# dw08aholes.net
KiCad netlist of a schematic drawn in EAGLE
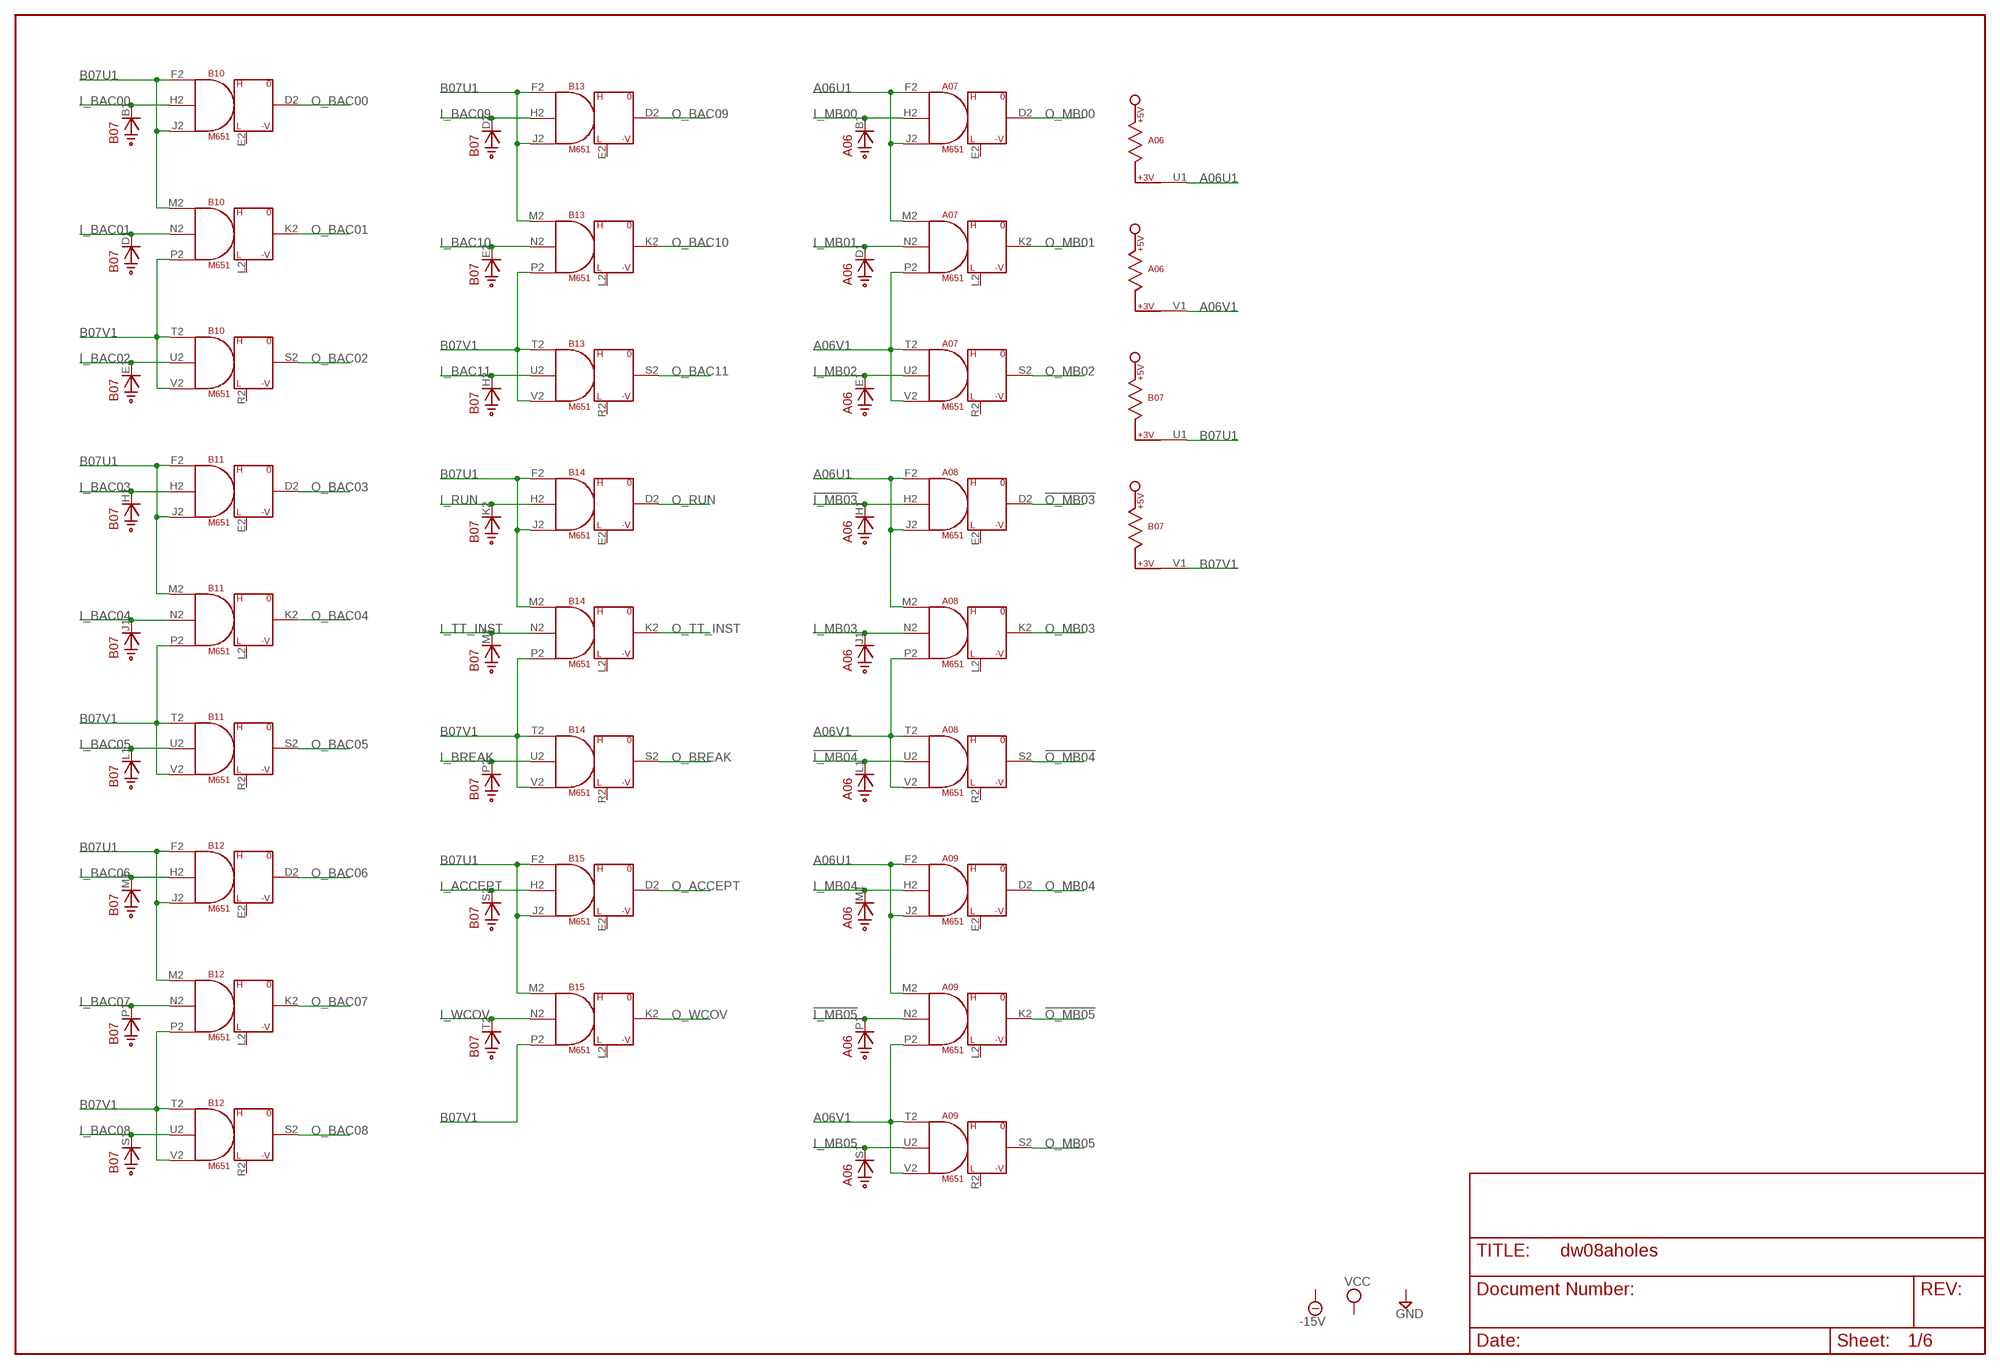
[diagram p0: schematic, sheet 1]
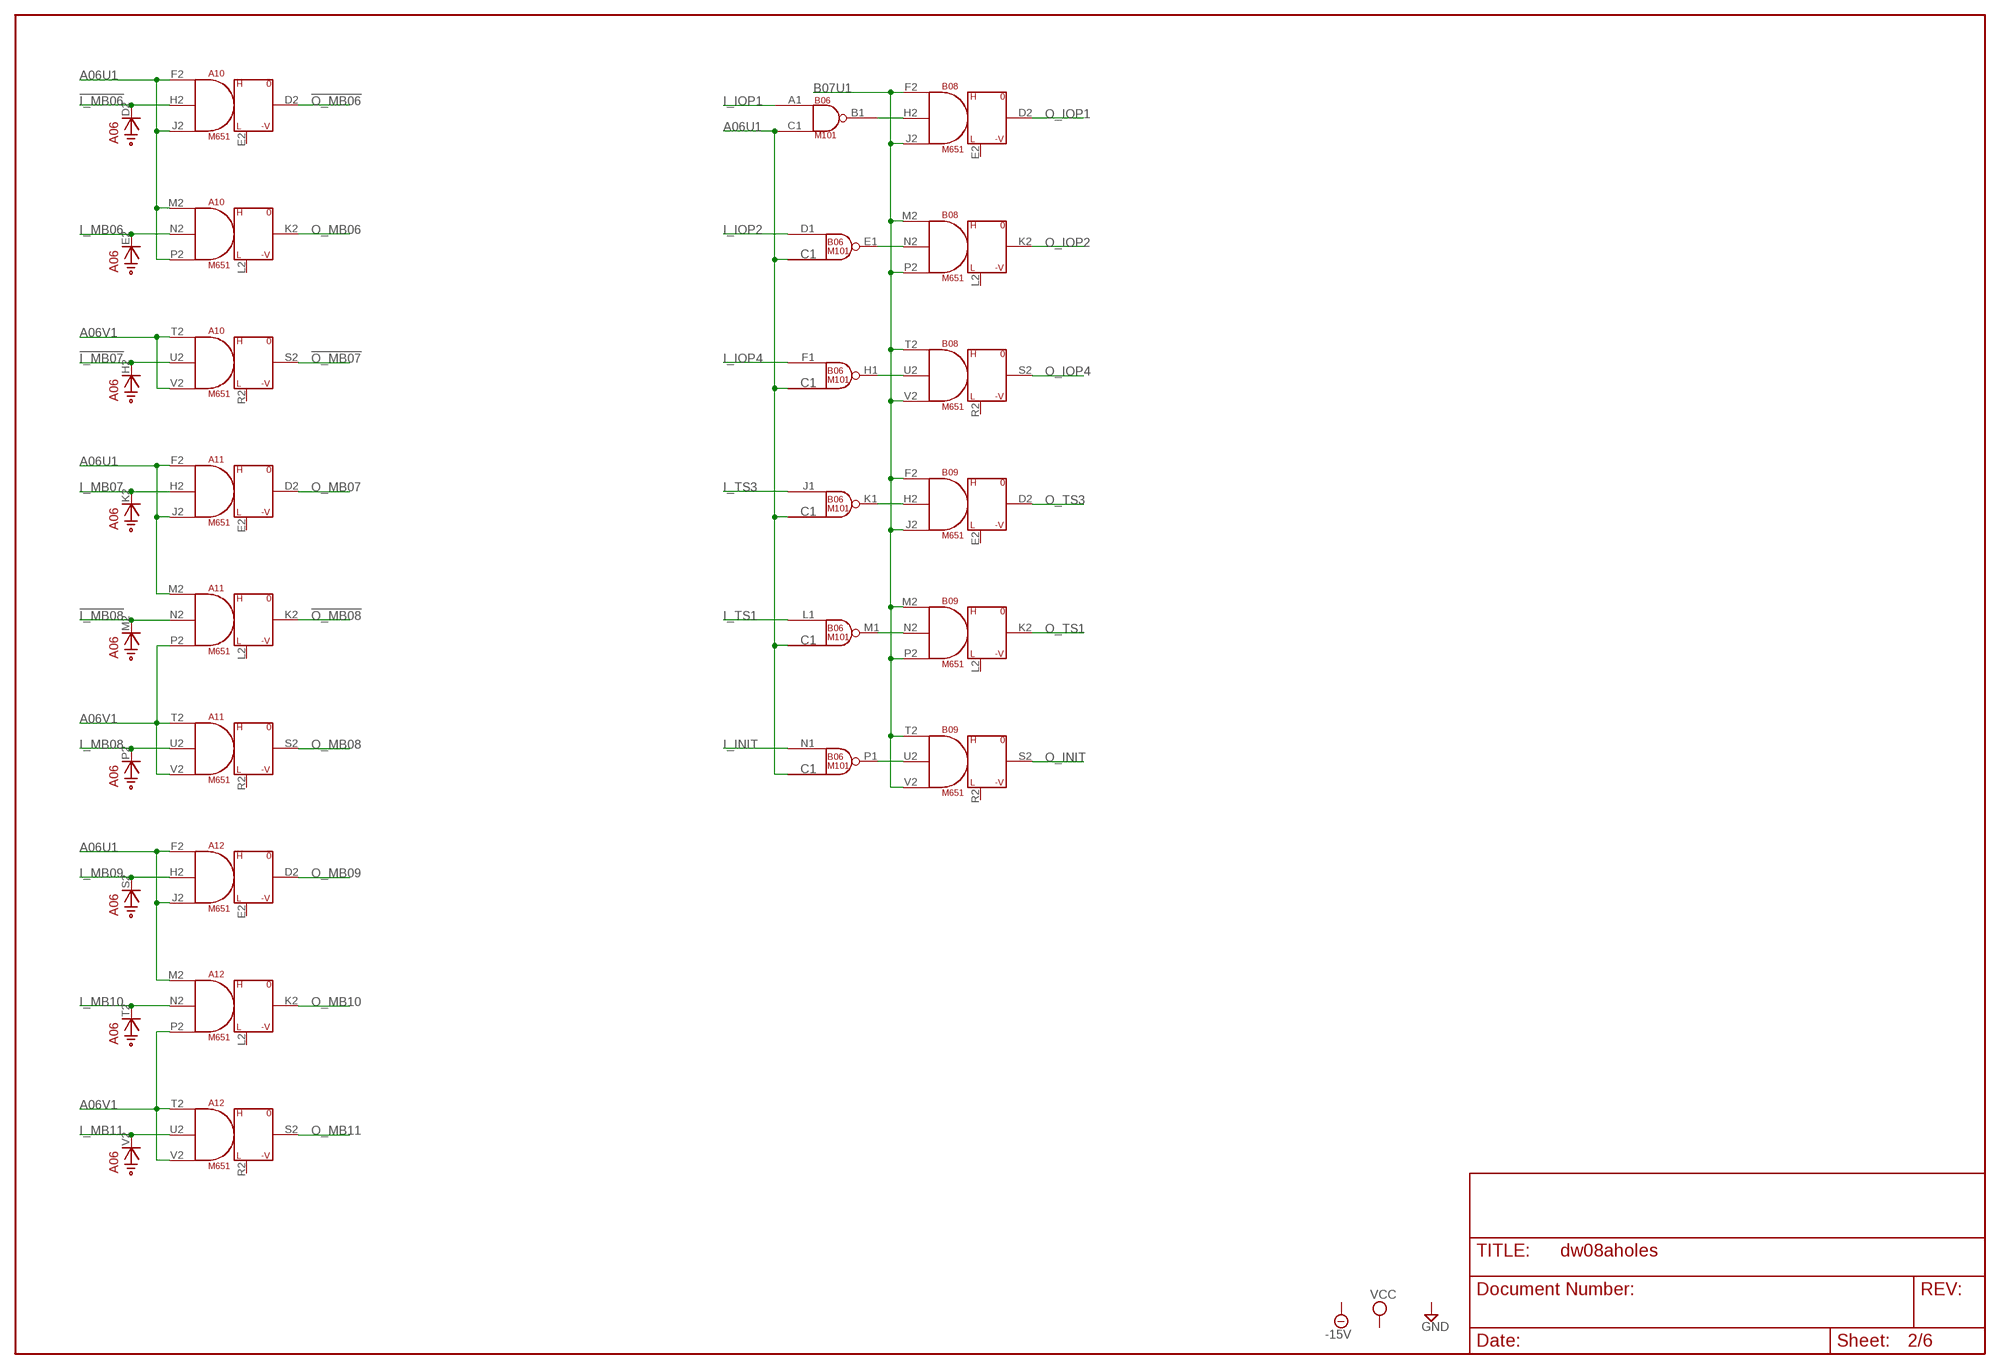
[diagram p1: schematic, sheet 2]
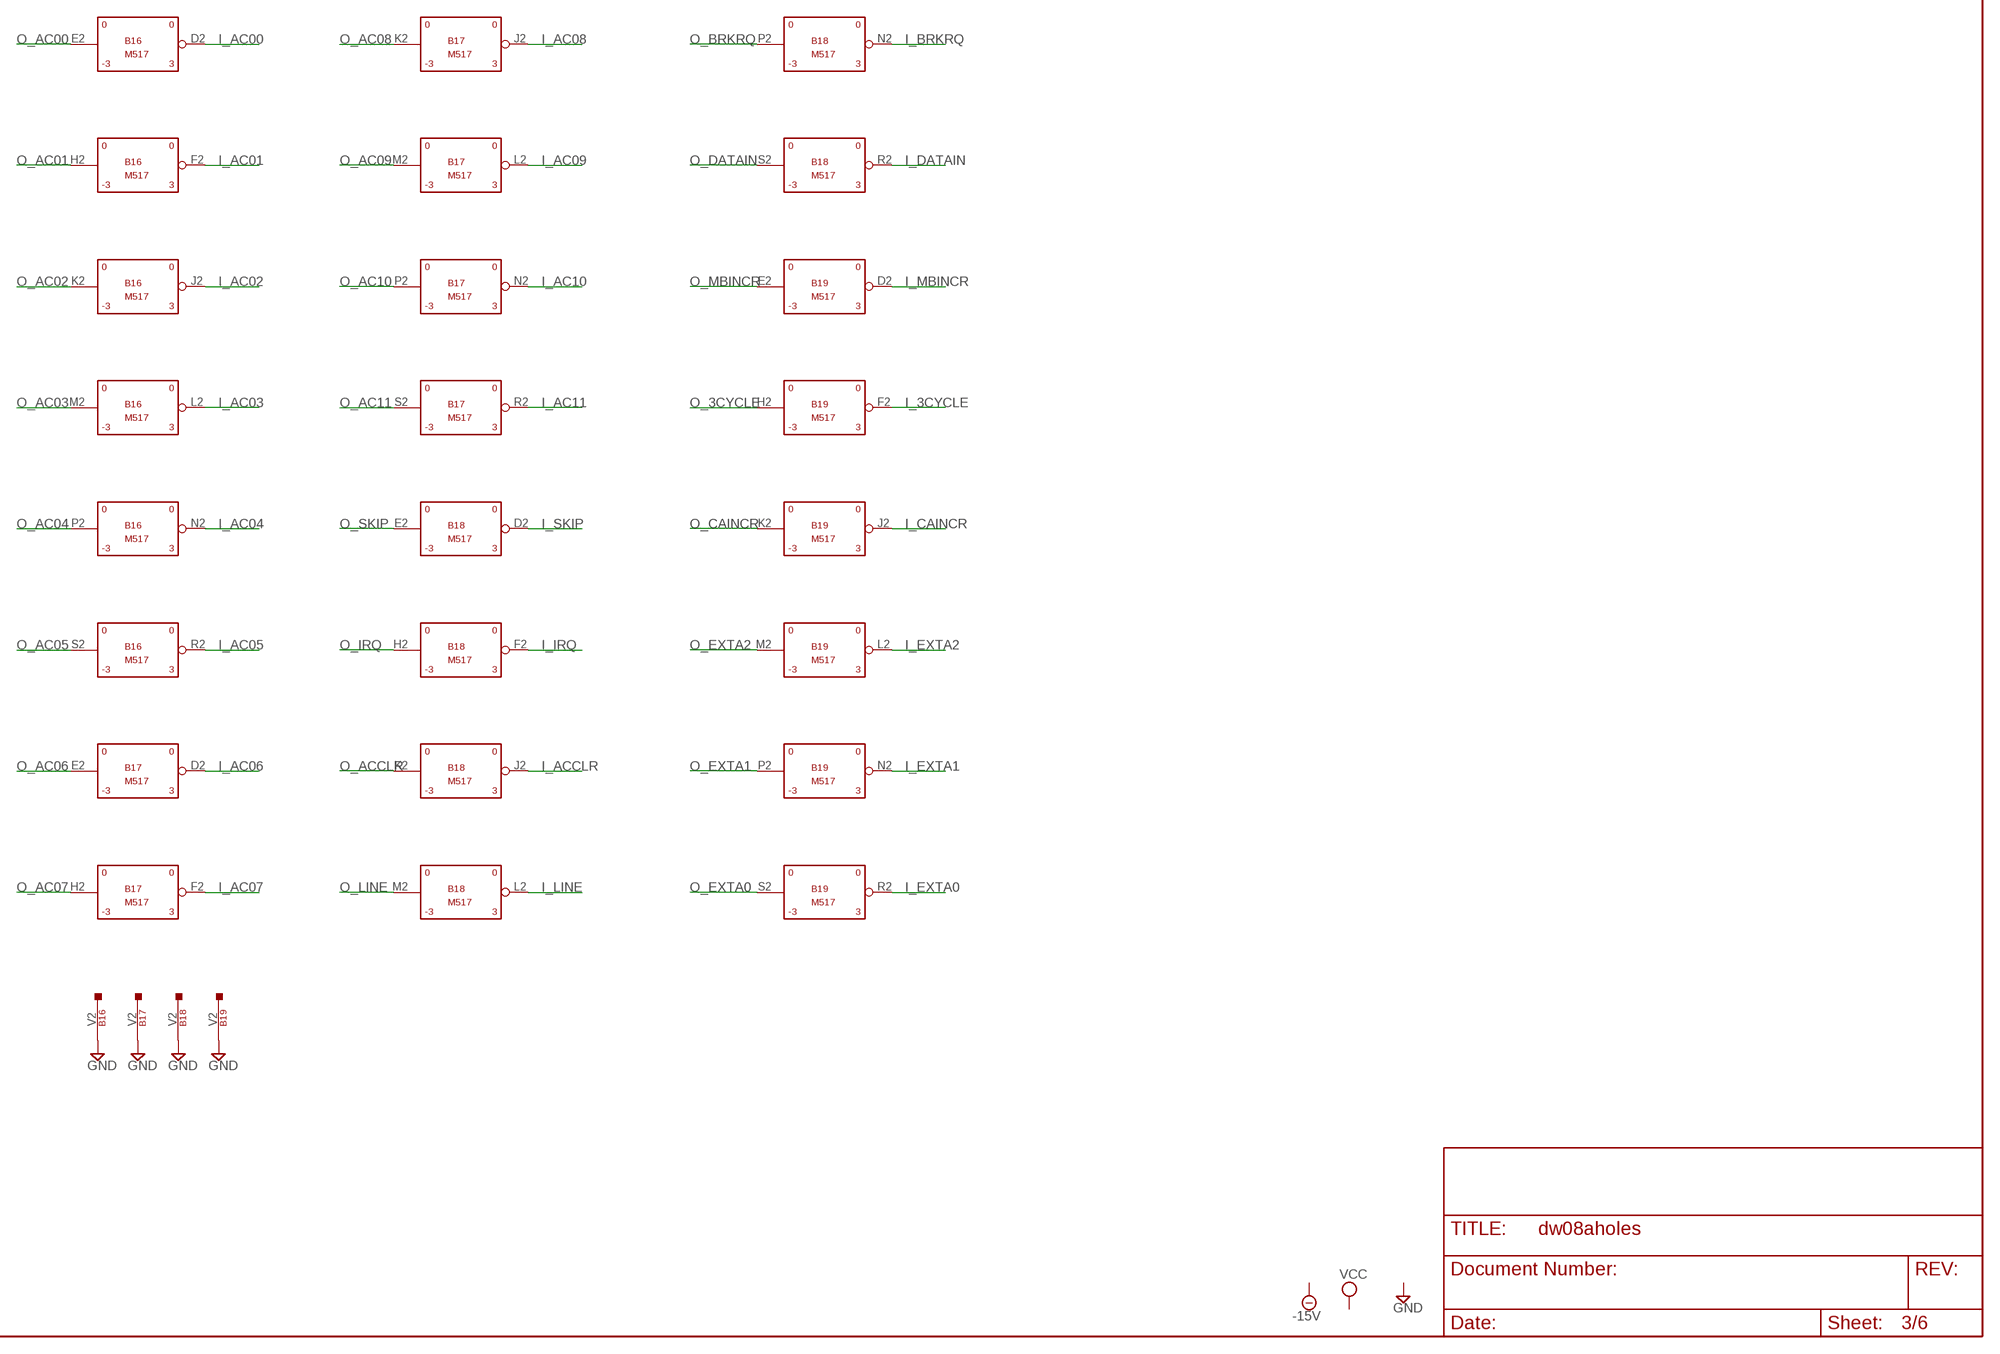
[diagram p2: schematic, sheet 3]
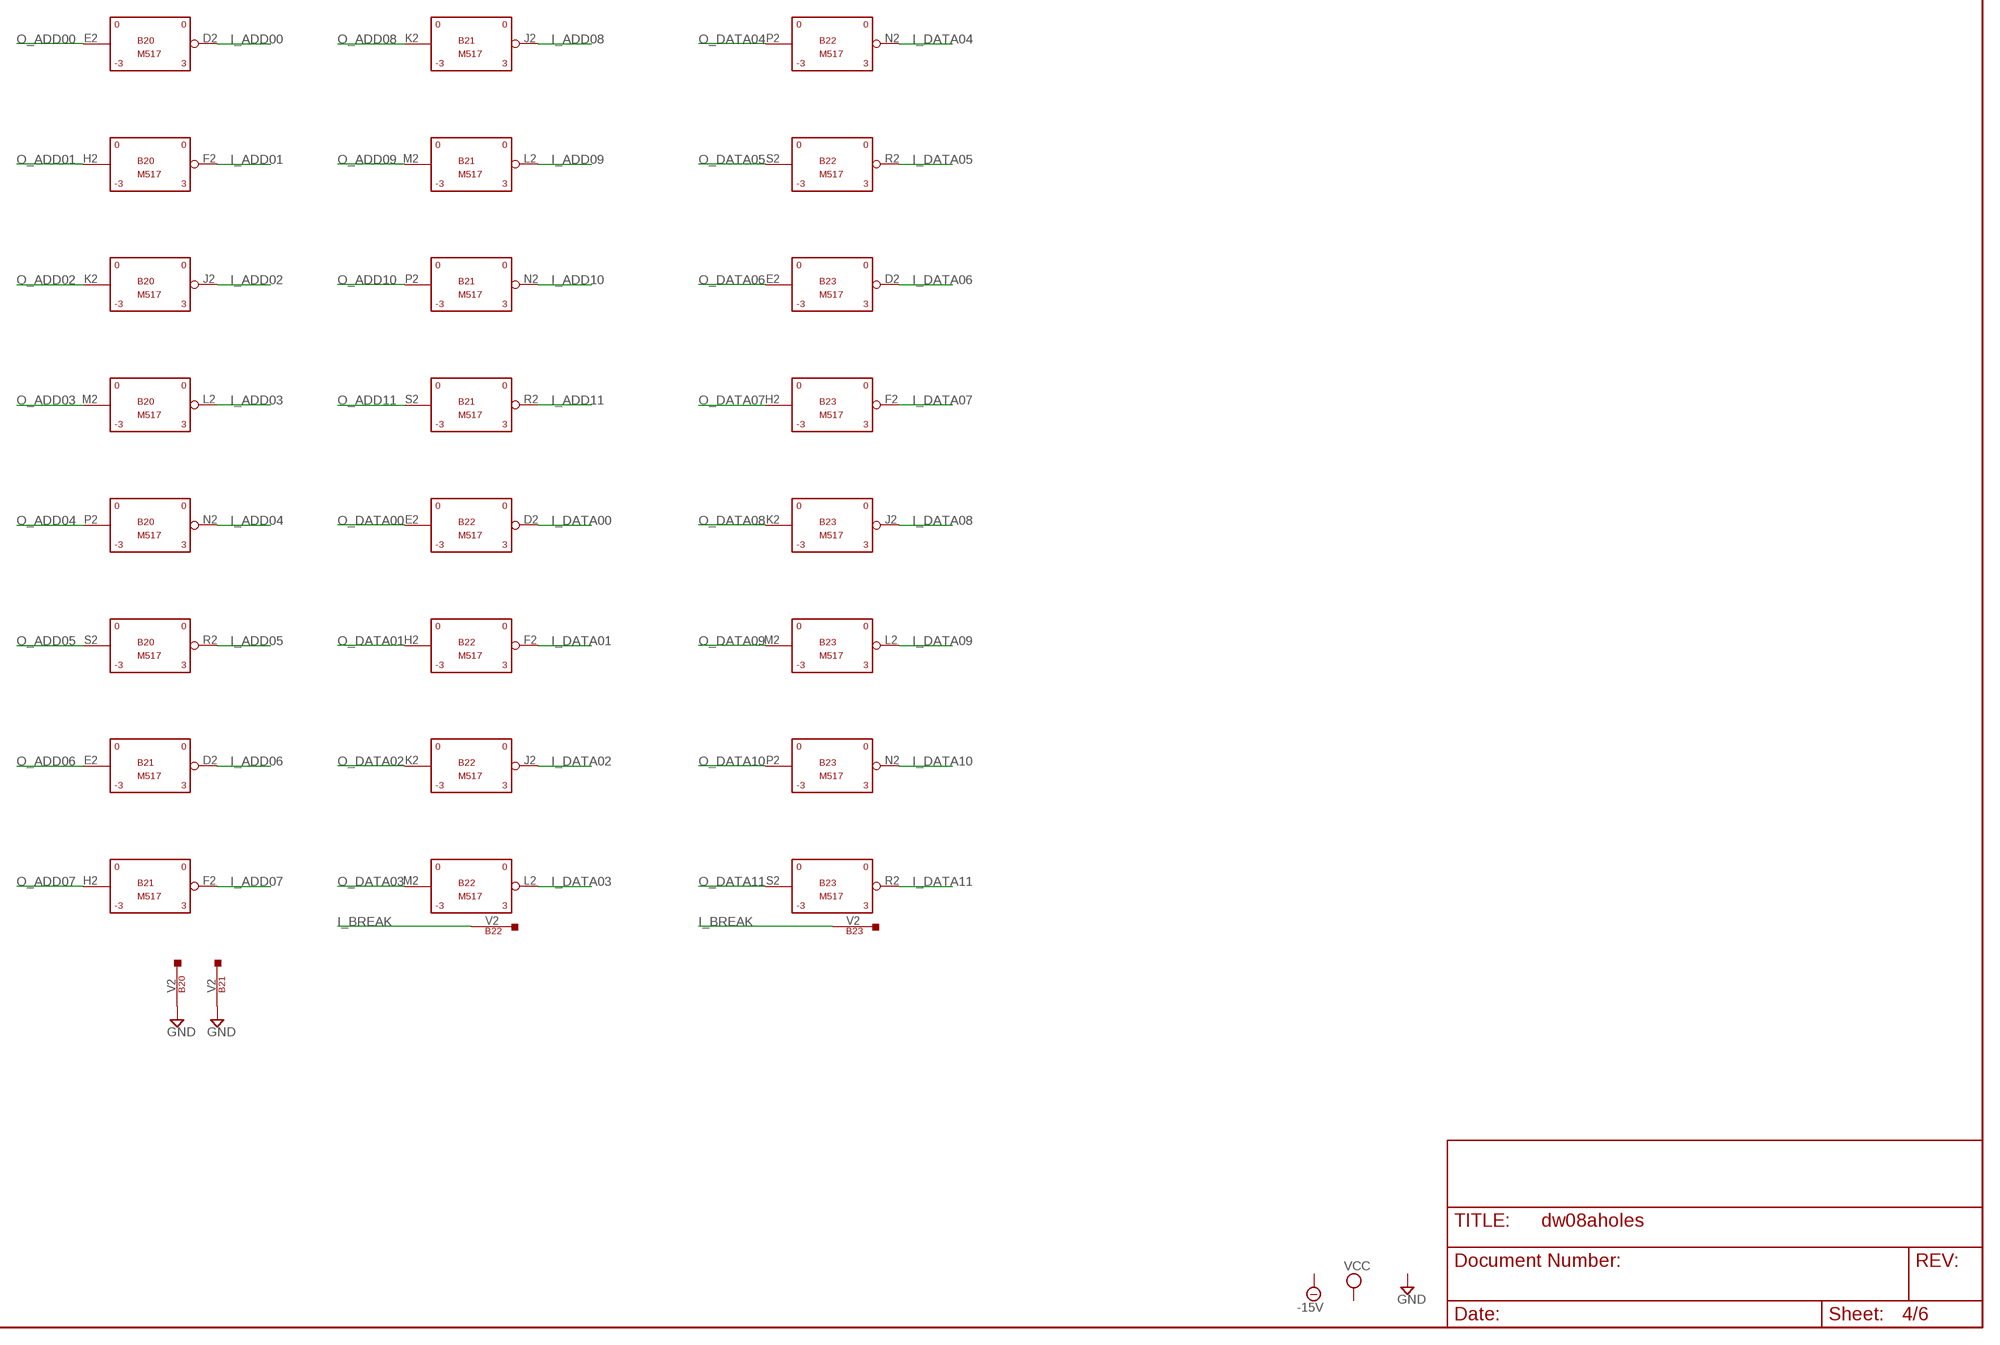
[diagram p3: schematic, sheet 4]
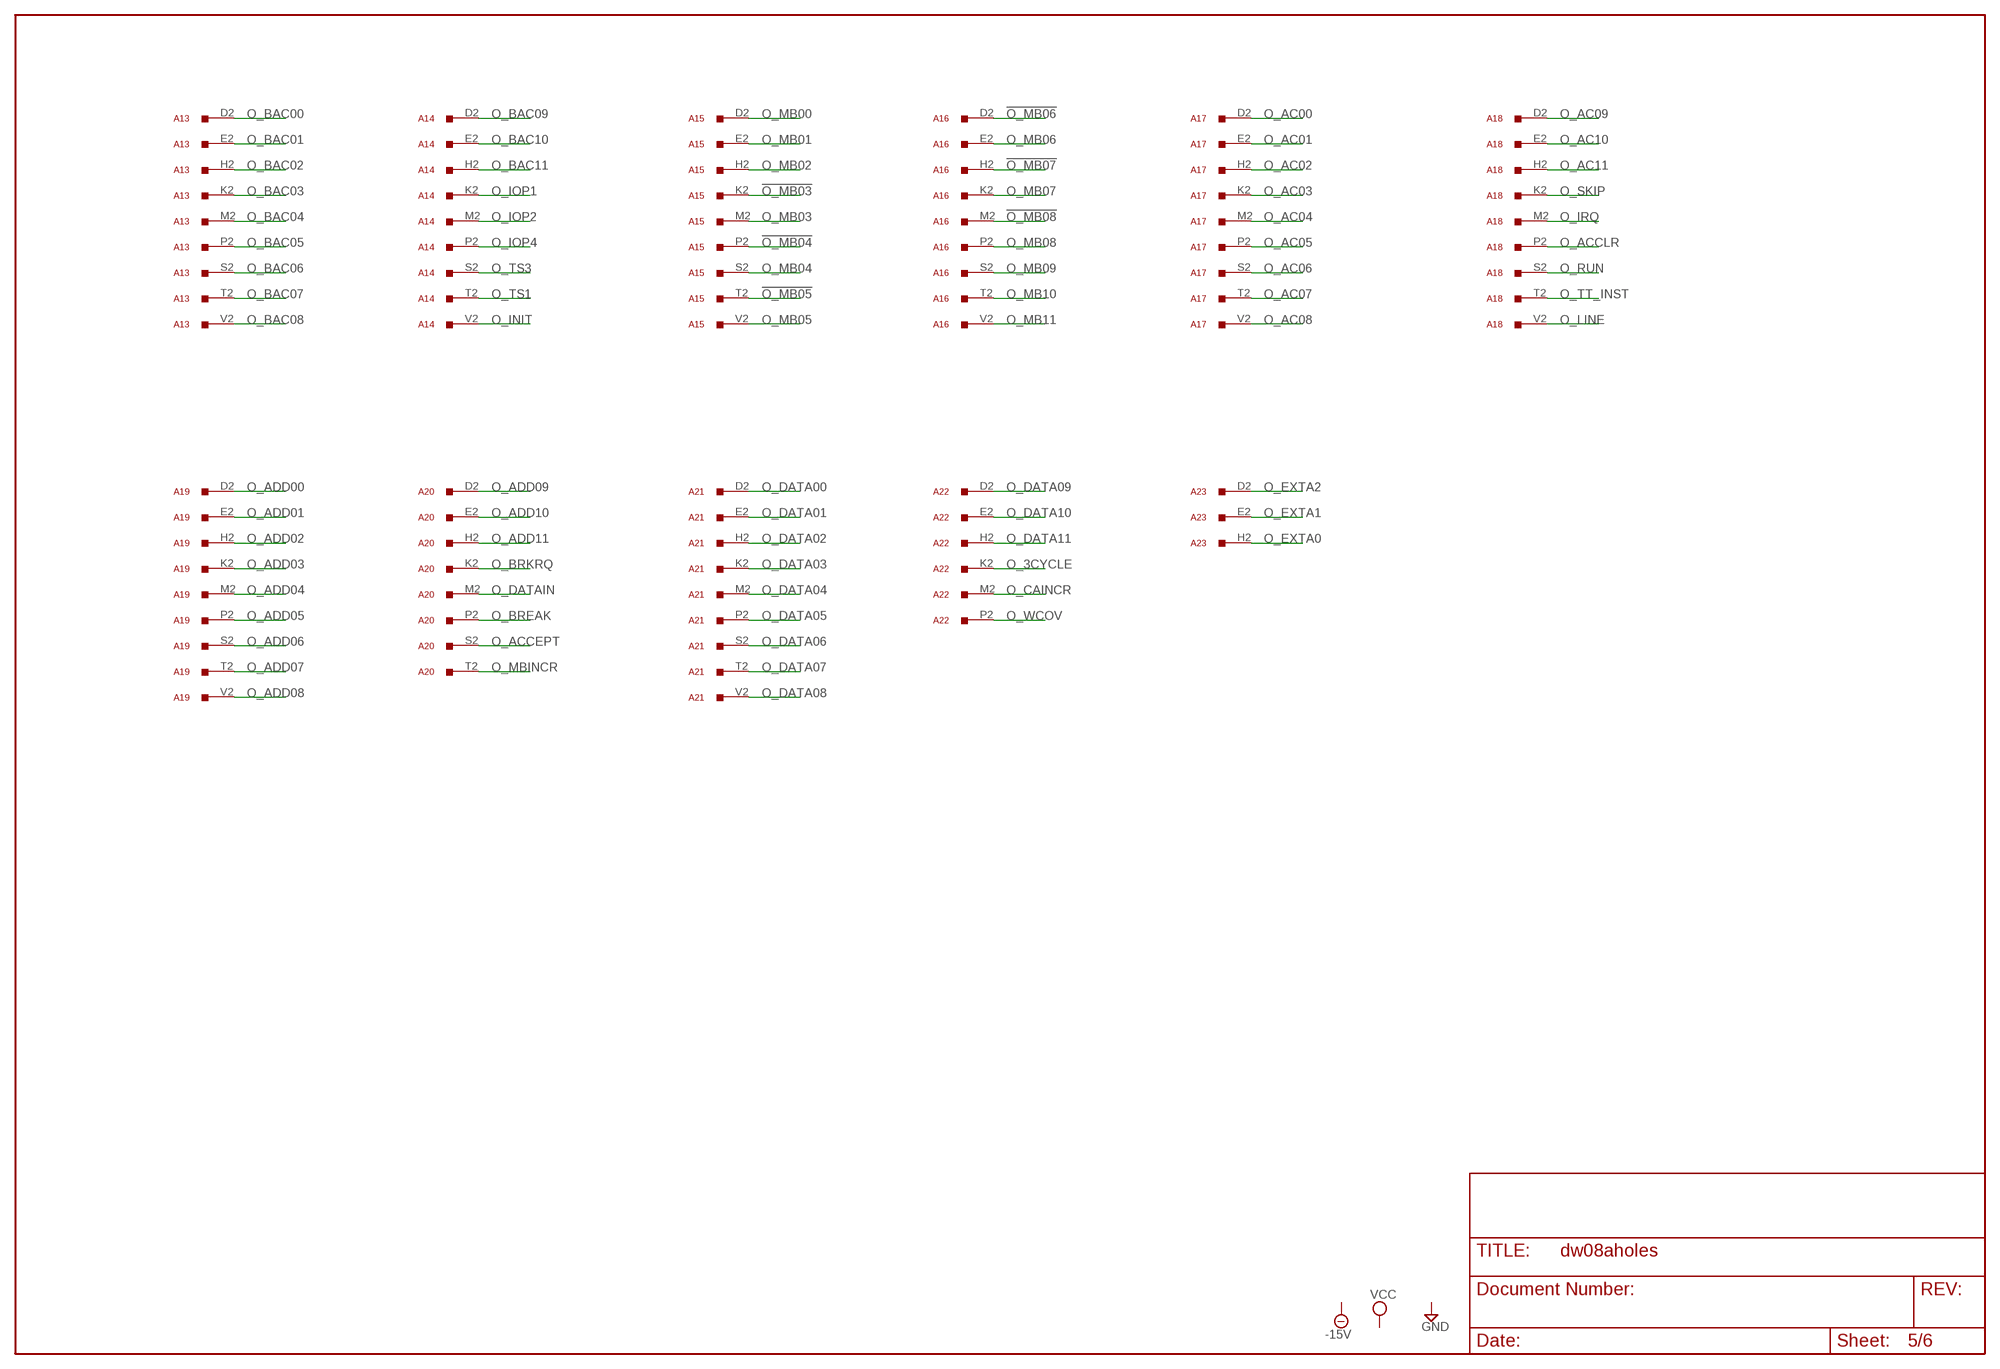
[diagram p4: schematic, sheet 5]
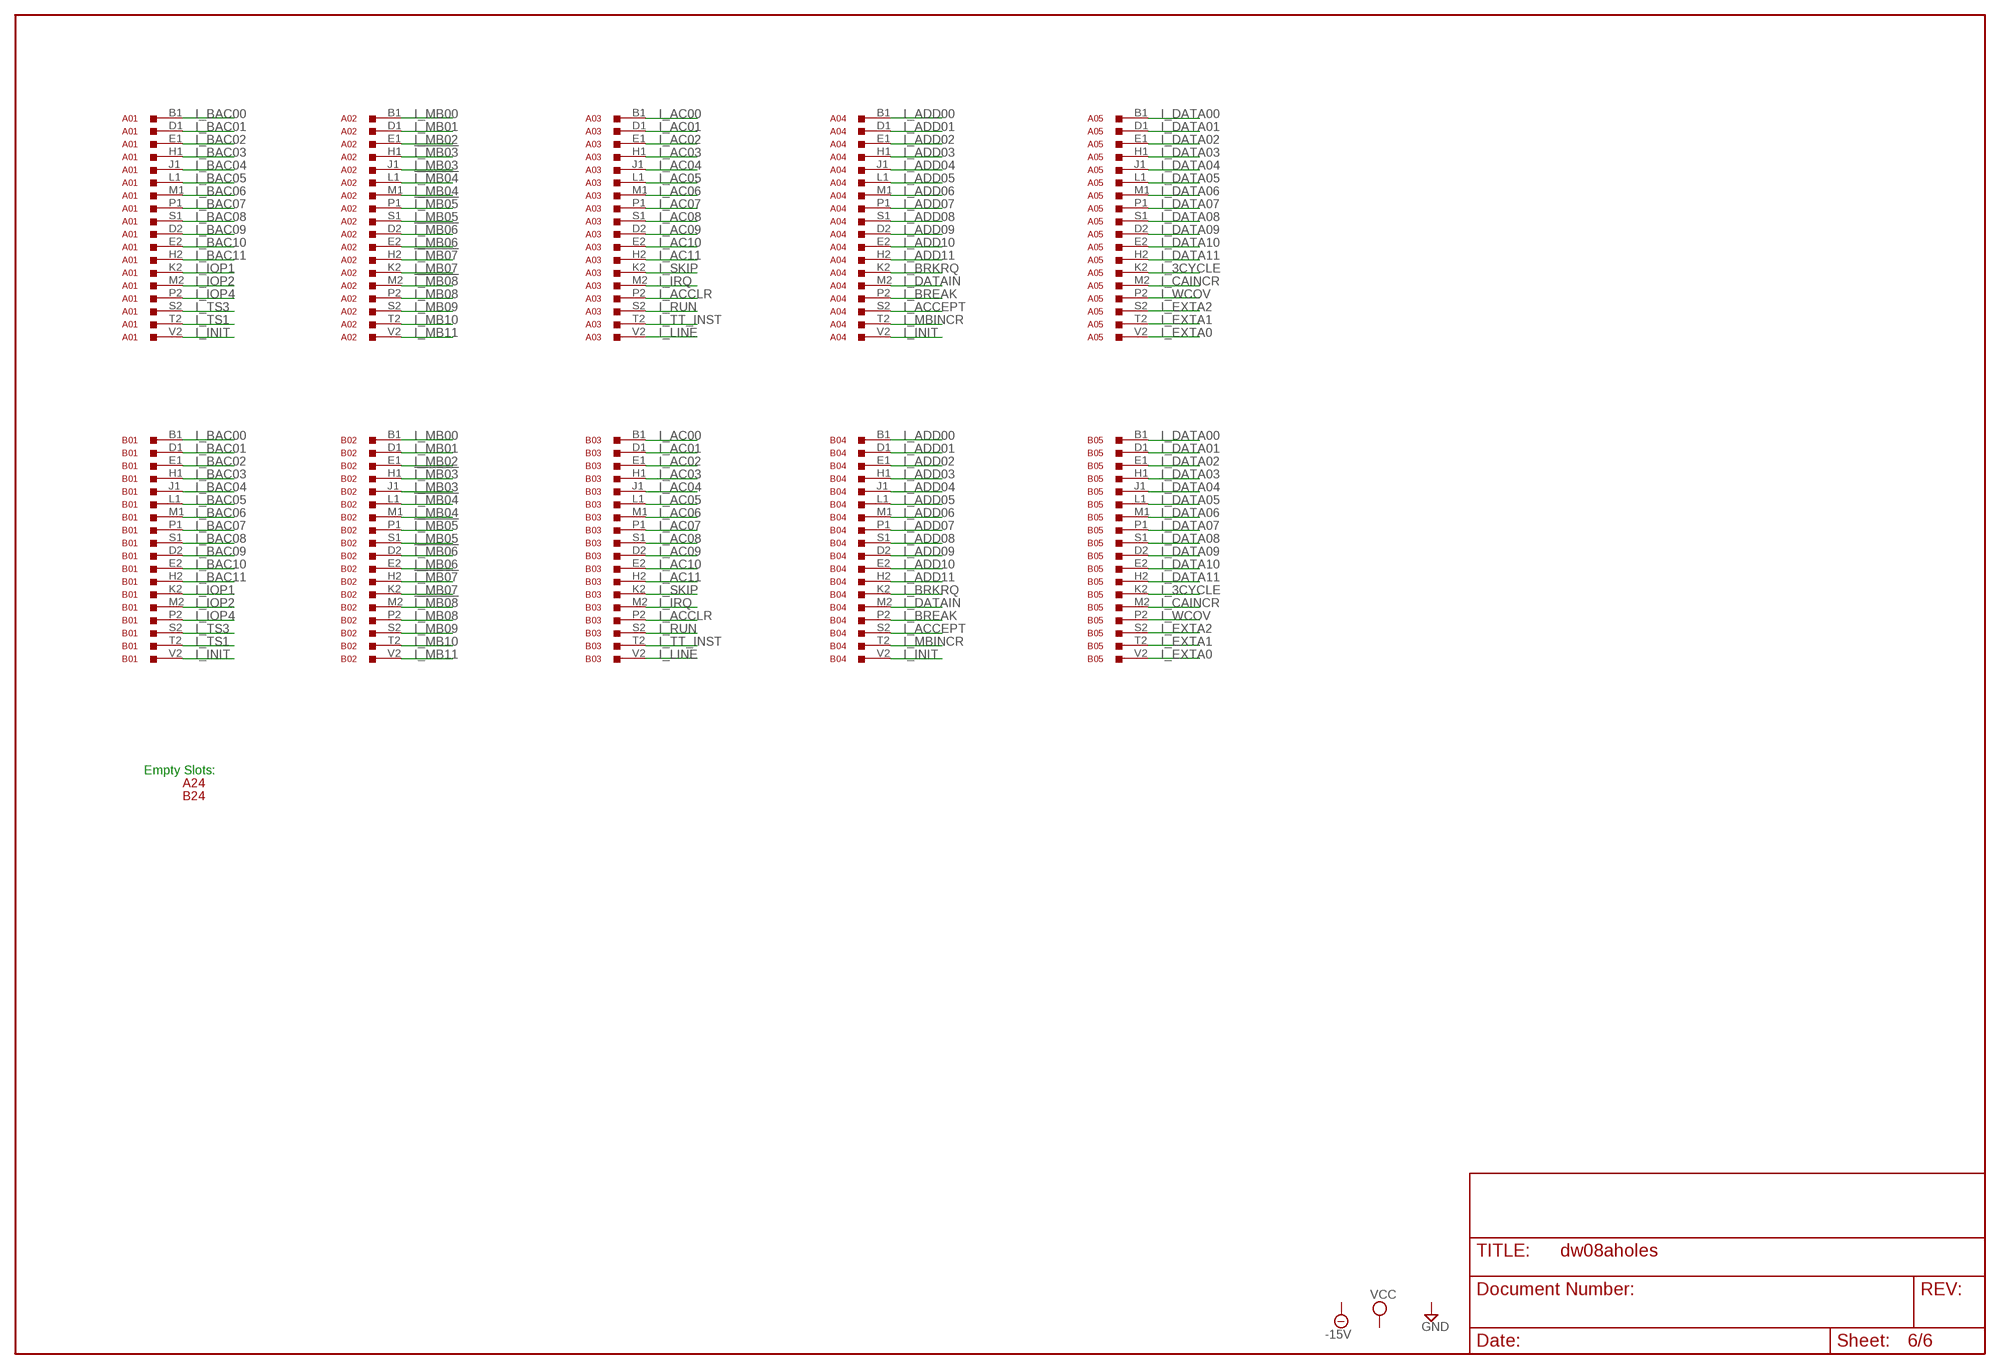
[diagram p5: schematic, sheet 6]

(export (version "E")
  (design (tool "Eeschema 10.0.6"))
  (components
    (comp (ref "A06")
      (value "M907")
      (footprint "eagle-import:H807")
      (libsource (lib "eagle-import") (part "M907"))
    )
    (comp (ref "A10")
      (value "M651")
      (footprint "eagle-import:H807")
      (libsource (lib "eagle-import") (part "M651"))
    )
    (comp (ref "A11")
      (value "M651")
      (footprint "eagle-import:H807")
      (libsource (lib "eagle-import") (part "M651"))
    )
    (comp (ref "A12")
      (value "M651")
      (footprint "eagle-import:H807")
      (libsource (lib "eagle-import") (part "M651"))
    )
    (comp (ref "B06")
      (value "M101")
      (footprint "eagle-import:H807")
      (libsource (lib "eagle-import") (part "M101"))
    )
    (comp (ref "B08")
      (value "M651")
      (footprint "eagle-import:H807")
      (libsource (lib "eagle-import") (part "M651"))
    )
    (comp (ref "B09")
      (value "M651")
      (footprint "eagle-import:H807")
      (libsource (lib "eagle-import") (part "M651"))
    )
    (comp (ref "A13")
      (value "W011")
      (footprint "eagle-import:H807")
      (libsource (lib "eagle-import") (part "W011"))
    )
    (comp (ref "A14")
      (value "W011")
      (footprint "eagle-import:H807")
      (libsource (lib "eagle-import") (part "W011"))
    )
    (comp (ref "A15")
      (value "W011")
      (footprint "eagle-import:H807")
      (libsource (lib "eagle-import") (part "W011"))
    )
    (comp (ref "A16")
      (value "W011")
      (footprint "eagle-import:H807")
      (libsource (lib "eagle-import") (part "W011"))
    )
    (comp (ref "A17")
      (value "W011")
      (footprint "eagle-import:H807")
      (libsource (lib "eagle-import") (part "W011"))
    )
    (comp (ref "A18")
      (value "W011")
      (footprint "eagle-import:H807")
      (libsource (lib "eagle-import") (part "W011"))
    )
    (comp (ref "A19")
      (value "W011")
      (footprint "eagle-import:H807")
      (libsource (lib "eagle-import") (part "W011"))
    )
    (comp (ref "A20")
      (value "W011")
      (footprint "eagle-import:H807")
      (libsource (lib "eagle-import") (part "W011"))
    )
    (comp (ref "A21")
      (value "W011")
      (footprint "eagle-import:H807")
      (libsource (lib "eagle-import") (part "W011"))
    )
    (comp (ref "A22")
      (value "W011")
      (footprint "eagle-import:H807")
      (libsource (lib "eagle-import") (part "W011"))
    )
    (comp (ref "A23")
      (value "W011")
      (footprint "eagle-import:H807")
      (libsource (lib "eagle-import") (part "W011"))
    )
    (comp (ref "B20")
      (value "M517")
      (footprint "eagle-import:H807")
      (libsource (lib "eagle-import") (part "M517"))
    )
    (comp (ref "B21")
      (value "M517")
      (footprint "eagle-import:H807")
      (libsource (lib "eagle-import") (part "M517"))
    )
    (comp (ref "B22")
      (value "M517")
      (footprint "eagle-import:H807")
      (libsource (lib "eagle-import") (part "M517"))
    )
    (comp (ref "B23")
      (value "M517")
      (footprint "eagle-import:H807")
      (libsource (lib "eagle-import") (part "M517"))
    )
    (comp (ref "A07")
      (value "M651")
      (footprint "eagle-import:H807")
      (libsource (lib "eagle-import") (part "M651"))
    )
    (comp (ref "A08")
      (value "M651")
      (footprint "eagle-import:H807")
      (libsource (lib "eagle-import") (part "M651"))
    )
    (comp (ref "A09")
      (value "M651")
      (footprint "eagle-import:H807")
      (libsource (lib "eagle-import") (part "M651"))
    )
    (comp (ref "B07")
      (value "M907")
      (footprint "eagle-import:H807")
      (libsource (lib "eagle-import") (part "M907"))
    )
    (comp (ref "B10")
      (value "M651")
      (footprint "eagle-import:H807")
      (libsource (lib "eagle-import") (part "M651"))
    )
    (comp (ref "B11")
      (value "M651")
      (footprint "eagle-import:H807")
      (libsource (lib "eagle-import") (part "M651"))
    )
    (comp (ref "B12")
      (value "M651")
      (footprint "eagle-import:H807")
      (libsource (lib "eagle-import") (part "M651"))
    )
    (comp (ref "B13")
      (value "M651")
      (footprint "eagle-import:H807")
      (libsource (lib "eagle-import") (part "M651"))
    )
    (comp (ref "B14")
      (value "M651")
      (footprint "eagle-import:H807")
      (libsource (lib "eagle-import") (part "M651"))
    )
    (comp (ref "B15")
      (value "M651")
      (footprint "eagle-import:H807")
      (libsource (lib "eagle-import") (part "M651"))
    )
    (comp (ref "A01")
      (value "M903")
      (footprint "eagle-import:H807")
      (libsource (lib "eagle-import") (part "M903"))
    )
    (comp (ref "A02")
      (value "M903")
      (footprint "eagle-import:H807")
      (libsource (lib "eagle-import") (part "M903"))
    )
    (comp (ref "A03")
      (value "M903")
      (footprint "eagle-import:H807")
      (libsource (lib "eagle-import") (part "M903"))
    )
    (comp (ref "A04")
      (value "M903")
      (footprint "eagle-import:H807")
      (libsource (lib "eagle-import") (part "M903"))
    )
    (comp (ref "A05")
      (value "M903")
      (footprint "eagle-import:H807")
      (libsource (lib "eagle-import") (part "M903"))
    )
    (comp (ref "A24")
      (value "H807")
      (footprint "eagle-import:H807")
      (libsource (lib "eagle-import") (part "H807"))
    )
    (comp (ref "B01")
      (value "M903")
      (footprint "eagle-import:H807")
      (libsource (lib "eagle-import") (part "M903"))
    )
    (comp (ref "B02")
      (value "M903")
      (footprint "eagle-import:H807")
      (libsource (lib "eagle-import") (part "M903"))
    )
    (comp (ref "B03")
      (value "M903")
      (footprint "eagle-import:H807")
      (libsource (lib "eagle-import") (part "M903"))
    )
    (comp (ref "B04")
      (value "M903")
      (footprint "eagle-import:H807")
      (libsource (lib "eagle-import") (part "M903"))
    )
    (comp (ref "B05")
      (value "M903")
      (footprint "eagle-import:H807")
      (libsource (lib "eagle-import") (part "M903"))
    )
    (comp (ref "B24")
      (value "H807")
      (footprint "eagle-import:H807")
      (libsource (lib "eagle-import") (part "H807"))
    )
    (comp (ref "B16")
      (value "M517")
      (footprint "eagle-import:H807")
      (libsource (lib "eagle-import") (part "M517"))
    )
    (comp (ref "B17")
      (value "M517")
      (footprint "eagle-import:H807")
      (libsource (lib "eagle-import") (part "M517"))
    )
    (comp (ref "B18")
      (value "M517")
      (footprint "eagle-import:H807")
      (libsource (lib "eagle-import") (part "M517"))
    )
    (comp (ref "B19")
      (value "M517")
      (footprint "eagle-import:H807")
      (libsource (lib "eagle-import") (part "M517"))
    )
  )
  (nets
    (net (code "2") (name "A06U1") (class "Default")
      (node (ref "A06") (pin "U1") (pinfunction "P$1_U1") (pintype "passive"))
      (node (ref "A07") (pin "F2") (pinfunction "IN1_F2") (pintype "input"))
      (node (ref "A07") (pin "J2") (pinfunction "IN3_J2") (pintype "input"))
      (node (ref "A07") (pin "M2") (pinfunction "IN1_M2") (pintype "input"))
      (node (ref "A08") (pin "F2") (pinfunction "IN1_F2") (pintype "input"))
      (node (ref "A08") (pin "J2") (pinfunction "IN3_J2") (pintype "input"))
      (node (ref "A08") (pin "M2") (pinfunction "IN1_M2") (pintype "input"))
      (node (ref "A09") (pin "F2") (pinfunction "IN1_F2") (pintype "input"))
      (node (ref "A09") (pin "J2") (pinfunction "IN3_J2") (pintype "input"))
      (node (ref "A09") (pin "M2") (pinfunction "IN1_M2") (pintype "input"))
      (node (ref "A10") (pin "F2") (pinfunction "IN1_F2") (pintype "input"))
      (node (ref "A10") (pin "J2") (pinfunction "IN3_J2") (pintype "input"))
      (node (ref "A10") (pin "M2") (pinfunction "IN1_M2") (pintype "input"))
      (node (ref "A10") (pin "P2") (pinfunction "IN3_P2") (pintype "input"))
      (node (ref "A11") (pin "F2") (pinfunction "IN1_F2") (pintype "input"))
      (node (ref "A11") (pin "J2") (pinfunction "IN3_J2") (pintype "input"))
      (node (ref "A11") (pin "M2") (pinfunction "IN1_M2") (pintype "input"))
      (node (ref "A12") (pin "F2") (pinfunction "IN1_F2") (pintype "input"))
      (node (ref "A12") (pin "J2") (pinfunction "IN3_J2") (pintype "input"))
      (node (ref "A12") (pin "M2") (pinfunction "IN1_M2") (pintype "input"))
      (node (ref "B06") (pin "C1") (pinfunction "IN2_C1") (pintype "input"))
    )
    (net (code "3") (name "A06V1") (class "Default")
      (node (ref "A06") (pin "V1") (pinfunction "P$1_V1") (pintype "passive"))
      (node (ref "A07") (pin "P2") (pinfunction "IN3_P2") (pintype "input"))
      (node (ref "A07") (pin "T2") (pinfunction "IN1_T2") (pintype "input"))
      (node (ref "A07") (pin "V2") (pinfunction "IN3_V2") (pintype "input"))
      (node (ref "A08") (pin "P2") (pinfunction "IN3_P2") (pintype "input"))
      (node (ref "A08") (pin "T2") (pinfunction "IN1_T2") (pintype "input"))
      (node (ref "A08") (pin "V2") (pinfunction "IN3_V2") (pintype "input"))
      (node (ref "A09") (pin "P2") (pinfunction "IN3_P2") (pintype "input"))
      (node (ref "A09") (pin "T2") (pinfunction "IN1_T2") (pintype "input"))
      (node (ref "A09") (pin "V2") (pinfunction "IN3_V2") (pintype "input"))
      (node (ref "A10") (pin "T2") (pinfunction "IN1_T2") (pintype "input"))
      (node (ref "A10") (pin "V2") (pinfunction "IN3_V2") (pintype "input"))
      (node (ref "A11") (pin "P2") (pinfunction "IN3_P2") (pintype "input"))
      (node (ref "A11") (pin "T2") (pinfunction "IN1_T2") (pintype "input"))
      (node (ref "A11") (pin "V2") (pinfunction "IN3_V2") (pintype "input"))
      (node (ref "A12") (pin "P2") (pinfunction "IN3_P2") (pintype "input"))
      (node (ref "A12") (pin "T2") (pinfunction "IN1_T2") (pintype "input"))
      (node (ref "A12") (pin "V2") (pinfunction "IN3_V2") (pintype "input"))
    )
    (net (code "4") (name "B07U1") (class "Default")
      (node (ref "B07") (pin "U1") (pinfunction "P$1_U1") (pintype "passive"))
      (node (ref "B08") (pin "F2") (pinfunction "IN1_F2") (pintype "input"))
      (node (ref "B08") (pin "J2") (pinfunction "IN3_J2") (pintype "input"))
      (node (ref "B08") (pin "M2") (pinfunction "IN1_M2") (pintype "input"))
      (node (ref "B08") (pin "P2") (pinfunction "IN3_P2") (pintype "input"))
      (node (ref "B08") (pin "T2") (pinfunction "IN1_T2") (pintype "input"))
      (node (ref "B08") (pin "V2") (pinfunction "IN3_V2") (pintype "input"))
      (node (ref "B09") (pin "F2") (pinfunction "IN1_F2") (pintype "input"))
      (node (ref "B09") (pin "J2") (pinfunction "IN3_J2") (pintype "input"))
      (node (ref "B09") (pin "M2") (pinfunction "IN1_M2") (pintype "input"))
      (node (ref "B09") (pin "P2") (pinfunction "IN3_P2") (pintype "input"))
      (node (ref "B09") (pin "T2") (pinfunction "IN1_T2") (pintype "input"))
      (node (ref "B09") (pin "V2") (pinfunction "IN3_V2") (pintype "input"))
      (node (ref "B10") (pin "F2") (pinfunction "IN1_F2") (pintype "input"))
      (node (ref "B10") (pin "J2") (pinfunction "IN3_J2") (pintype "input"))
      (node (ref "B10") (pin "M2") (pinfunction "IN1_M2") (pintype "input"))
      (node (ref "B11") (pin "F2") (pinfunction "IN1_F2") (pintype "input"))
      (node (ref "B11") (pin "J2") (pinfunction "IN3_J2") (pintype "input"))
      (node (ref "B11") (pin "M2") (pinfunction "IN1_M2") (pintype "input"))
      (node (ref "B12") (pin "F2") (pinfunction "IN1_F2") (pintype "input"))
      (node (ref "B12") (pin "J2") (pinfunction "IN3_J2") (pintype "input"))
      (node (ref "B12") (pin "M2") (pinfunction "IN1_M2") (pintype "input"))
      (node (ref "B13") (pin "F2") (pinfunction "IN1_F2") (pintype "input"))
      (node (ref "B13") (pin "J2") (pinfunction "IN3_J2") (pintype "input"))
      (node (ref "B13") (pin "M2") (pinfunction "IN1_M2") (pintype "input"))
      (node (ref "B14") (pin "F2") (pinfunction "IN1_F2") (pintype "input"))
      (node (ref "B14") (pin "J2") (pinfunction "IN3_J2") (pintype "input"))
      (node (ref "B14") (pin "M2") (pinfunction "IN1_M2") (pintype "input"))
      (node (ref "B15") (pin "F2") (pinfunction "IN1_F2") (pintype "input"))
      (node (ref "B15") (pin "J2") (pinfunction "IN3_J2") (pintype "input"))
      (node (ref "B15") (pin "M2") (pinfunction "IN1_M2") (pintype "input"))
    )
    (net (code "5") (name "B07V1") (class "Default")
      (node (ref "B07") (pin "V1") (pinfunction "P$1_V1") (pintype "passive"))
      (node (ref "B10") (pin "P2") (pinfunction "IN3_P2") (pintype "input"))
      (node (ref "B10") (pin "T2") (pinfunction "IN1_T2") (pintype "input"))
      (node (ref "B10") (pin "V2") (pinfunction "IN3_V2") (pintype "input"))
      (node (ref "B11") (pin "P2") (pinfunction "IN3_P2") (pintype "input"))
      (node (ref "B11") (pin "T2") (pinfunction "IN1_T2") (pintype "input"))
      (node (ref "B11") (pin "V2") (pinfunction "IN3_V2") (pintype "input"))
      (node (ref "B12") (pin "P2") (pinfunction "IN3_P2") (pintype "input"))
      (node (ref "B12") (pin "T2") (pinfunction "IN1_T2") (pintype "input"))
      (node (ref "B12") (pin "V2") (pinfunction "IN3_V2") (pintype "input"))
      (node (ref "B13") (pin "P2") (pinfunction "IN3_P2") (pintype "input"))
      (node (ref "B13") (pin "T2") (pinfunction "IN1_T2") (pintype "input"))
      (node (ref "B13") (pin "V2") (pinfunction "IN3_V2") (pintype "input"))
      (node (ref "B14") (pin "P2") (pinfunction "IN3_P2") (pintype "input"))
      (node (ref "B14") (pin "T2") (pinfunction "IN1_T2") (pintype "input"))
      (node (ref "B14") (pin "V2") (pinfunction "IN3_V2") (pintype "input"))
      (node (ref "B15") (pin "P2") (pinfunction "IN3_P2") (pintype "input"))
    )
    (net (code "6") (name "GND") (class "Default")
      (node (ref "B16") (pin "V2") (pinfunction "P$1_V2") (pintype "input"))
      (node (ref "B17") (pin "V2") (pinfunction "P$1_V2") (pintype "input"))
      (node (ref "B18") (pin "V2") (pinfunction "P$1_V2") (pintype "input"))
      (node (ref "B19") (pin "V2") (pinfunction "P$1_V2") (pintype "input"))
      (node (ref "B20") (pin "V2") (pinfunction "P$1_V2") (pintype "input"))
      (node (ref "B21") (pin "V2") (pinfunction "P$1_V2") (pintype "input"))
    )
    (net (code "7") (name "I_3CYCLE") (class "Default")
      (node (ref "A05") (pin "K2") (pinfunction "P$2_K2") (pintype "bidirectional"))
      (node (ref "B05") (pin "K2") (pinfunction "P$2_K2") (pintype "bidirectional"))
      (node (ref "B19") (pin "F2") (pinfunction "OUT_F2") (pintype "output"))
    )
    (net (code "8") (name "I_AC00") (class "Default")
      (node (ref "A03") (pin "B1") (pinfunction "P$2_B1") (pintype "bidirectional"))
      (node (ref "B03") (pin "B1") (pinfunction "P$2_B1") (pintype "bidirectional"))
      (node (ref "B16") (pin "D2") (pinfunction "OUT_D2") (pintype "output"))
    )
    (net (code "9") (name "I_AC01") (class "Default")
      (node (ref "A03") (pin "D1") (pinfunction "P$2_D1") (pintype "bidirectional"))
      (node (ref "B03") (pin "D1") (pinfunction "P$2_D1") (pintype "bidirectional"))
      (node (ref "B16") (pin "F2") (pinfunction "OUT_F2") (pintype "output"))
    )
    (net (code "10") (name "I_AC02") (class "Default")
      (node (ref "A03") (pin "E1") (pinfunction "P$2_E1") (pintype "bidirectional"))
      (node (ref "B03") (pin "E1") (pinfunction "P$2_E1") (pintype "bidirectional"))
      (node (ref "B16") (pin "J2") (pinfunction "OUT_J2") (pintype "output"))
    )
    (net (code "11") (name "I_AC03") (class "Default")
      (node (ref "A03") (pin "H1") (pinfunction "P$2_H1") (pintype "bidirectional"))
      (node (ref "B03") (pin "H1") (pinfunction "P$2_H1") (pintype "bidirectional"))
      (node (ref "B16") (pin "L2") (pinfunction "OUT_L2") (pintype "output"))
    )
    (net (code "12") (name "I_AC04") (class "Default")
      (node (ref "A03") (pin "J1") (pinfunction "P$2_J1") (pintype "bidirectional"))
      (node (ref "B03") (pin "J1") (pinfunction "P$2_J1") (pintype "bidirectional"))
      (node (ref "B16") (pin "N2") (pinfunction "OUT_N2") (pintype "output"))
    )
    (net (code "13") (name "I_AC05") (class "Default")
      (node (ref "A03") (pin "L1") (pinfunction "P$2_L1") (pintype "bidirectional"))
      (node (ref "B03") (pin "L1") (pinfunction "P$2_L1") (pintype "bidirectional"))
      (node (ref "B16") (pin "R2") (pinfunction "OUT_R2") (pintype "output"))
    )
    (net (code "14") (name "I_AC06") (class "Default")
      (node (ref "A03") (pin "M1") (pinfunction "P$2_M1") (pintype "bidirectional"))
      (node (ref "B03") (pin "M1") (pinfunction "P$2_M1") (pintype "bidirectional"))
      (node (ref "B17") (pin "D2") (pinfunction "OUT_D2") (pintype "output"))
    )
    (net (code "15") (name "I_AC07") (class "Default")
      (node (ref "A03") (pin "P1") (pinfunction "P$2_P1") (pintype "bidirectional"))
      (node (ref "B03") (pin "P1") (pinfunction "P$2_P1") (pintype "bidirectional"))
      (node (ref "B17") (pin "F2") (pinfunction "OUT_F2") (pintype "output"))
    )
    (net (code "16") (name "I_AC08") (class "Default")
      (node (ref "A03") (pin "S1") (pinfunction "P$2_S1") (pintype "bidirectional"))
      (node (ref "B03") (pin "S1") (pinfunction "P$2_S1") (pintype "bidirectional"))
      (node (ref "B17") (pin "J2") (pinfunction "OUT_J2") (pintype "output"))
    )
    (net (code "17") (name "I_AC09") (class "Default")
      (node (ref "A03") (pin "D2") (pinfunction "P$2_D2") (pintype "bidirectional"))
      (node (ref "B03") (pin "D2") (pinfunction "P$2_D2") (pintype "bidirectional"))
      (node (ref "B17") (pin "L2") (pinfunction "OUT_L2") (pintype "output"))
    )
    (net (code "18") (name "I_AC10") (class "Default")
      (node (ref "A03") (pin "E2") (pinfunction "P$2_E2") (pintype "bidirectional"))
      (node (ref "B03") (pin "E2") (pinfunction "P$2_E2") (pintype "bidirectional"))
      (node (ref "B17") (pin "N2") (pinfunction "OUT_N2") (pintype "output"))
    )
    (net (code "19") (name "I_AC11") (class "Default")
      (node (ref "A03") (pin "H2") (pinfunction "P$2_H2") (pintype "bidirectional"))
      (node (ref "B03") (pin "H2") (pinfunction "P$2_H2") (pintype "bidirectional"))
      (node (ref "B17") (pin "R2") (pinfunction "OUT_R2") (pintype "output"))
    )
    (net (code "20") (name "I_ACCEPT") (class "Default")
      (node (ref "A04") (pin "S2") (pinfunction "P$2_S2") (pintype "bidirectional"))
      (node (ref "B04") (pin "S2") (pinfunction "P$2_S2") (pintype "bidirectional"))
      (node (ref "B07") (pin "S2") (pinfunction "CATHODE_S2") (pintype "passive"))
      (node (ref "B15") (pin "H2") (pinfunction "IN2_H2") (pintype "input"))
    )
    (net (code "21") (name "I_ACCLR") (class "Default")
      (node (ref "A03") (pin "P2") (pinfunction "P$2_P2") (pintype "bidirectional"))
      (node (ref "B03") (pin "P2") (pinfunction "P$2_P2") (pintype "bidirectional"))
      (node (ref "B18") (pin "J2") (pinfunction "OUT_J2") (pintype "output"))
    )
    (net (code "22") (name "I_ADD00") (class "Default")
      (node (ref "A04") (pin "B1") (pinfunction "P$2_B1") (pintype "bidirectional"))
      (node (ref "B04") (pin "B1") (pinfunction "P$2_B1") (pintype "bidirectional"))
      (node (ref "B20") (pin "D2") (pinfunction "OUT_D2") (pintype "output"))
    )
    (net (code "23") (name "I_ADD01") (class "Default")
      (node (ref "A04") (pin "D1") (pinfunction "P$2_D1") (pintype "bidirectional"))
      (node (ref "B04") (pin "D1") (pinfunction "P$2_D1") (pintype "bidirectional"))
      (node (ref "B20") (pin "F2") (pinfunction "OUT_F2") (pintype "output"))
    )
    (net (code "24") (name "I_ADD02") (class "Default")
      (node (ref "A04") (pin "E1") (pinfunction "P$2_E1") (pintype "bidirectional"))
      (node (ref "B04") (pin "E1") (pinfunction "P$2_E1") (pintype "bidirectional"))
      (node (ref "B20") (pin "J2") (pinfunction "OUT_J2") (pintype "output"))
    )
    (net (code "25") (name "I_ADD03") (class "Default")
      (node (ref "A04") (pin "H1") (pinfunction "P$2_H1") (pintype "bidirectional"))
      (node (ref "B04") (pin "H1") (pinfunction "P$2_H1") (pintype "bidirectional"))
      (node (ref "B20") (pin "L2") (pinfunction "OUT_L2") (pintype "output"))
    )
    (net (code "26") (name "I_ADD04") (class "Default")
      (node (ref "A04") (pin "J1") (pinfunction "P$2_J1") (pintype "bidirectional"))
      (node (ref "B04") (pin "J1") (pinfunction "P$2_J1") (pintype "bidirectional"))
      (node (ref "B20") (pin "N2") (pinfunction "OUT_N2") (pintype "output"))
    )
    (net (code "27") (name "I_ADD05") (class "Default")
      (node (ref "A04") (pin "L1") (pinfunction "P$2_L1") (pintype "bidirectional"))
      (node (ref "B04") (pin "L1") (pinfunction "P$2_L1") (pintype "bidirectional"))
      (node (ref "B20") (pin "R2") (pinfunction "OUT_R2") (pintype "output"))
    )
    (net (code "28") (name "I_ADD06") (class "Default")
      (node (ref "A04") (pin "M1") (pinfunction "P$2_M1") (pintype "bidirectional"))
      (node (ref "B04") (pin "M1") (pinfunction "P$2_M1") (pintype "bidirectional"))
      (node (ref "B21") (pin "D2") (pinfunction "OUT_D2") (pintype "output"))
    )
    (net (code "29") (name "I_ADD07") (class "Default")
      (node (ref "A04") (pin "P1") (pinfunction "P$2_P1") (pintype "bidirectional"))
      (node (ref "B04") (pin "P1") (pinfunction "P$2_P1") (pintype "bidirectional"))
      (node (ref "B21") (pin "F2") (pinfunction "OUT_F2") (pintype "output"))
    )
    (net (code "30") (name "I_ADD08") (class "Default")
      (node (ref "A04") (pin "S1") (pinfunction "P$2_S1") (pintype "bidirectional"))
      (node (ref "B04") (pin "S1") (pinfunction "P$2_S1") (pintype "bidirectional"))
      (node (ref "B21") (pin "J2") (pinfunction "OUT_J2") (pintype "output"))
    )
    (net (code "31") (name "I_ADD09") (class "Default")
      (node (ref "A04") (pin "D2") (pinfunction "P$2_D2") (pintype "bidirectional"))
      (node (ref "B04") (pin "D2") (pinfunction "P$2_D2") (pintype "bidirectional"))
      (node (ref "B21") (pin "L2") (pinfunction "OUT_L2") (pintype "output"))
    )
    (net (code "32") (name "I_ADD10") (class "Default")
      (node (ref "A04") (pin "E2") (pinfunction "P$2_E2") (pintype "bidirectional"))
      (node (ref "B04") (pin "E2") (pinfunction "P$2_E2") (pintype "bidirectional"))
      (node (ref "B21") (pin "N2") (pinfunction "OUT_N2") (pintype "output"))
    )
    (net (code "33") (name "I_ADD11") (class "Default")
      (node (ref "A04") (pin "H2") (pinfunction "P$2_H2") (pintype "bidirectional"))
      (node (ref "B04") (pin "H2") (pinfunction "P$2_H2") (pintype "bidirectional"))
      (node (ref "B21") (pin "R2") (pinfunction "OUT_R2") (pintype "output"))
    )
    (net (code "34") (name "I_BAC00") (class "Default")
      (node (ref "A01") (pin "B1") (pinfunction "P$2_B1") (pintype "bidirectional"))
      (node (ref "B01") (pin "B1") (pinfunction "P$2_B1") (pintype "bidirectional"))
      (node (ref "B07") (pin "B1") (pinfunction "CATHODE_B1") (pintype "passive"))
      (node (ref "B10") (pin "H2") (pinfunction "IN2_H2") (pintype "input"))
    )
    (net (code "35") (name "I_BAC01") (class "Default")
      (node (ref "A01") (pin "D1") (pinfunction "P$2_D1") (pintype "bidirectional"))
      (node (ref "B01") (pin "D1") (pinfunction "P$2_D1") (pintype "bidirectional"))
      (node (ref "B07") (pin "D1") (pinfunction "CATHODE_D1") (pintype "passive"))
      (node (ref "B10") (pin "N2") (pinfunction "IN2_N2") (pintype "input"))
    )
    (net (code "36") (name "I_BAC02") (class "Default")
      (node (ref "A01") (pin "E1") (pinfunction "P$2_E1") (pintype "bidirectional"))
      (node (ref "B01") (pin "E1") (pinfunction "P$2_E1") (pintype "bidirectional"))
      (node (ref "B07") (pin "E1") (pinfunction "CATHODE_E1") (pintype "passive"))
      (node (ref "B10") (pin "U2") (pinfunction "IN2_U2") (pintype "input"))
    )
    (net (code "37") (name "I_BAC03") (class "Default")
      (node (ref "A01") (pin "H1") (pinfunction "P$2_H1") (pintype "bidirectional"))
      (node (ref "B01") (pin "H1") (pinfunction "P$2_H1") (pintype "bidirectional"))
      (node (ref "B07") (pin "H1") (pinfunction "CATHODE_H1") (pintype "passive"))
      (node (ref "B11") (pin "H2") (pinfunction "IN2_H2") (pintype "input"))
    )
    (net (code "38") (name "I_BAC04") (class "Default")
      (node (ref "A01") (pin "J1") (pinfunction "P$2_J1") (pintype "bidirectional"))
      (node (ref "B01") (pin "J1") (pinfunction "P$2_J1") (pintype "bidirectional"))
      (node (ref "B07") (pin "J1") (pinfunction "CATHODE_J1") (pintype "passive"))
      (node (ref "B11") (pin "N2") (pinfunction "IN2_N2") (pintype "input"))
    )
    (net (code "39") (name "I_BAC05") (class "Default")
      (node (ref "A01") (pin "L1") (pinfunction "P$2_L1") (pintype "bidirectional"))
      (node (ref "B01") (pin "L1") (pinfunction "P$2_L1") (pintype "bidirectional"))
      (node (ref "B07") (pin "L1") (pinfunction "CATHODE_L1") (pintype "passive"))
      (node (ref "B11") (pin "U2") (pinfunction "IN2_U2") (pintype "input"))
    )
    (net (code "40") (name "I_BAC06") (class "Default")
      (node (ref "A01") (pin "M1") (pinfunction "P$2_M1") (pintype "bidirectional"))
      (node (ref "B01") (pin "M1") (pinfunction "P$2_M1") (pintype "bidirectional"))
      (node (ref "B07") (pin "M1") (pinfunction "CATHODE_M1") (pintype "passive"))
      (node (ref "B12") (pin "H2") (pinfunction "IN2_H2") (pintype "input"))
    )
    (net (code "41") (name "I_BAC07") (class "Default")
      (node (ref "A01") (pin "P1") (pinfunction "P$2_P1") (pintype "bidirectional"))
      (node (ref "B01") (pin "P1") (pinfunction "P$2_P1") (pintype "bidirectional"))
      (node (ref "B07") (pin "P1") (pinfunction "CATHODE_P1") (pintype "passive"))
      (node (ref "B12") (pin "N2") (pinfunction "IN2_N2") (pintype "input"))
    )
    (net (code "42") (name "I_BAC08") (class "Default")
      (node (ref "A01") (pin "S1") (pinfunction "P$2_S1") (pintype "bidirectional"))
      (node (ref "B01") (pin "S1") (pinfunction "P$2_S1") (pintype "bidirectional"))
      (node (ref "B07") (pin "S1") (pinfunction "CATHODE_S1") (pintype "passive"))
      (node (ref "B12") (pin "U2") (pinfunction "IN2_U2") (pintype "input"))
    )
    (net (code "43") (name "I_BAC09") (class "Default")
      (node (ref "A01") (pin "D2") (pinfunction "P$2_D2") (pintype "bidirectional"))
      (node (ref "B01") (pin "D2") (pinfunction "P$2_D2") (pintype "bidirectional"))
      (node (ref "B07") (pin "D2") (pinfunction "CATHODE_D2") (pintype "passive"))
      (node (ref "B13") (pin "H2") (pinfunction "IN2_H2") (pintype "input"))
    )
    (net (code "44") (name "I_BAC10") (class "Default")
      (node (ref "A01") (pin "E2") (pinfunction "P$2_E2") (pintype "bidirectional"))
      (node (ref "B01") (pin "E2") (pinfunction "P$2_E2") (pintype "bidirectional"))
      (node (ref "B07") (pin "E2") (pinfunction "CATHODE_E2") (pintype "passive"))
      (node (ref "B13") (pin "N2") (pinfunction "IN2_N2") (pintype "input"))
    )
    (net (code "45") (name "I_BAC11") (class "Default")
      (node (ref "A01") (pin "H2") (pinfunction "P$2_H2") (pintype "bidirectional"))
      (node (ref "B01") (pin "H2") (pinfunction "P$2_H2") (pintype "bidirectional"))
      (node (ref "B07") (pin "H2") (pinfunction "CATHODE_H2") (pintype "passive"))
      (node (ref "B13") (pin "U2") (pinfunction "IN2_U2") (pintype "input"))
    )
    (net (code "46") (name "I_BREAK") (class "Default")
      (node (ref "A04") (pin "P2") (pinfunction "P$2_P2") (pintype "bidirectional"))
      (node (ref "B04") (pin "P2") (pinfunction "P$2_P2") (pintype "bidirectional"))
      (node (ref "B07") (pin "P2") (pinfunction "CATHODE_P2") (pintype "passive"))
      (node (ref "B14") (pin "U2") (pinfunction "IN2_U2") (pintype "input"))
      (node (ref "B22") (pin "V2") (pinfunction "P$1_V2") (pintype "input"))
      (node (ref "B23") (pin "V2") (pinfunction "P$1_V2") (pintype "input"))
    )
    (net (code "47") (name "I_BRKRQ") (class "Default")
      (node (ref "A04") (pin "K2") (pinfunction "P$2_K2") (pintype "bidirectional"))
      (node (ref "B04") (pin "K2") (pinfunction "P$2_K2") (pintype "bidirectional"))
      (node (ref "B18") (pin "N2") (pinfunction "OUT_N2") (pintype "output"))
    )
    (net (code "48") (name "I_CAINCR") (class "Default")
      (node (ref "A05") (pin "M2") (pinfunction "P$2_M2") (pintype "bidirectional"))
      (node (ref "B05") (pin "M2") (pinfunction "P$2_M2") (pintype "bidirectional"))
      (node (ref "B19") (pin "J2") (pinfunction "OUT_J2") (pintype "output"))
    )
    (net (code "49") (name "I_DATA00") (class "Default")
      (node (ref "A05") (pin "B1") (pinfunction "P$2_B1") (pintype "bidirectional"))
      (node (ref "B05") (pin "B1") (pinfunction "P$2_B1") (pintype "bidirectional"))
      (node (ref "B22") (pin "D2") (pinfunction "OUT_D2") (pintype "output"))
    )
    (net (code "50") (name "I_DATA01") (class "Default")
      (node (ref "A05") (pin "D1") (pinfunction "P$2_D1") (pintype "bidirectional"))
      (node (ref "B05") (pin "D1") (pinfunction "P$2_D1") (pintype "bidirectional"))
      (node (ref "B22") (pin "F2") (pinfunction "OUT_F2") (pintype "output"))
    )
    (net (code "51") (name "I_DATA02") (class "Default")
      (node (ref "A05") (pin "E1") (pinfunction "P$2_E1") (pintype "bidirectional"))
      (node (ref "B05") (pin "E1") (pinfunction "P$2_E1") (pintype "bidirectional"))
      (node (ref "B22") (pin "J2") (pinfunction "OUT_J2") (pintype "output"))
    )
    (net (code "52") (name "I_DATA03") (class "Default")
      (node (ref "A05") (pin "H1") (pinfunction "P$2_H1") (pintype "bidirectional"))
      (node (ref "B05") (pin "H1") (pinfunction "P$2_H1") (pintype "bidirectional"))
      (node (ref "B22") (pin "L2") (pinfunction "OUT_L2") (pintype "output"))
    )
    (net (code "53") (name "I_DATA04") (class "Default")
      (node (ref "A05") (pin "J1") (pinfunction "P$2_J1") (pintype "bidirectional"))
      (node (ref "B05") (pin "J1") (pinfunction "P$2_J1") (pintype "bidirectional"))
      (node (ref "B22") (pin "N2") (pinfunction "OUT_N2") (pintype "output"))
    )
    (net (code "54") (name "I_DATA05") (class "Default")
      (node (ref "A05") (pin "L1") (pinfunction "P$2_L1") (pintype "bidirectional"))
      (node (ref "B05") (pin "L1") (pinfunction "P$2_L1") (pintype "bidirectional"))
      (node (ref "B22") (pin "R2") (pinfunction "OUT_R2") (pintype "output"))
    )
    (net (code "55") (name "I_DATA06") (class "Default")
      (node (ref "A05") (pin "M1") (pinfunction "P$2_M1") (pintype "bidirectional"))
      (node (ref "B05") (pin "M1") (pinfunction "P$2_M1") (pintype "bidirectional"))
      (node (ref "B23") (pin "D2") (pinfunction "OUT_D2") (pintype "output"))
    )
    (net (code "56") (name "I_DATA07") (class "Default")
      (node (ref "A05") (pin "P1") (pinfunction "P$2_P1") (pintype "bidirectional"))
      (node (ref "B05") (pin "P1") (pinfunction "P$2_P1") (pintype "bidirectional"))
      (node (ref "B23") (pin "F2") (pinfunction "OUT_F2") (pintype "output"))
    )
    (net (code "57") (name "I_DATA08") (class "Default")
      (node (ref "A05") (pin "S1") (pinfunction "P$2_S1") (pintype "bidirectional"))
      (node (ref "B05") (pin "S1") (pinfunction "P$2_S1") (pintype "bidirectional"))
      (node (ref "B23") (pin "J2") (pinfunction "OUT_J2") (pintype "output"))
    )
    (net (code "58") (name "I_DATA09") (class "Default")
      (node (ref "A05") (pin "D2") (pinfunction "P$2_D2") (pintype "bidirectional"))
      (node (ref "B05") (pin "D2") (pinfunction "P$2_D2") (pintype "bidirectional"))
      (node (ref "B23") (pin "L2") (pinfunction "OUT_L2") (pintype "output"))
    )
    (net (code "59") (name "I_DATA10") (class "Default")
      (node (ref "A05") (pin "E2") (pinfunction "P$2_E2") (pintype "bidirectional"))
      (node (ref "B05") (pin "E2") (pinfunction "P$2_E2") (pintype "bidirectional"))
      (node (ref "B23") (pin "N2") (pinfunction "OUT_N2") (pintype "output"))
    )
    (net (code "60") (name "I_DATA11") (class "Default")
      (node (ref "A05") (pin "H2") (pinfunction "P$2_H2") (pintype "bidirectional"))
      (node (ref "B05") (pin "H2") (pinfunction "P$2_H2") (pintype "bidirectional"))
      (node (ref "B23") (pin "R2") (pinfunction "OUT_R2") (pintype "output"))
    )
    (net (code "61") (name "I_DATAIN") (class "Default")
      (node (ref "A04") (pin "M2") (pinfunction "P$2_M2") (pintype "bidirectional"))
      (node (ref "B04") (pin "M2") (pinfunction "P$2_M2") (pintype "bidirectional"))
      (node (ref "B18") (pin "R2") (pinfunction "OUT_R2") (pintype "output"))
    )
    (net (code "62") (name "I_EXTA0") (class "Default")
      (node (ref "A05") (pin "V2") (pinfunction "P$2_V2") (pintype "bidirectional"))
      (node (ref "B05") (pin "V2") (pinfunction "P$2_V2") (pintype "bidirectional"))
      (node (ref "B19") (pin "R2") (pinfunction "OUT_R2") (pintype "output"))
    )
    (net (code "63") (name "I_EXTA1") (class "Default")
      (node (ref "A05") (pin "T2") (pinfunction "P$2_T2") (pintype "bidirectional"))
      (node (ref "B05") (pin "T2") (pinfunction "P$2_T2") (pintype "bidirectional"))
      (node (ref "B19") (pin "N2") (pinfunction "OUT_N2") (pintype "output"))
    )
    (net (code "64") (name "I_EXTA2") (class "Default")
      (node (ref "A05") (pin "S2") (pinfunction "P$2_S2") (pintype "bidirectional"))
      (node (ref "B05") (pin "S2") (pinfunction "P$2_S2") (pintype "bidirectional"))
      (node (ref "B19") (pin "L2") (pinfunction "OUT_L2") (pintype "output"))
    )
    (net (code "65") (name "I_INIT") (class "Default")
      (node (ref "A01") (pin "V2") (pinfunction "P$2_V2") (pintype "bidirectional"))
      (node (ref "A04") (pin "V2") (pinfunction "P$2_V2") (pintype "bidirectional"))
      (node (ref "B01") (pin "V2") (pinfunction "P$2_V2") (pintype "bidirectional"))
      (node (ref "B04") (pin "V2") (pinfunction "P$2_V2") (pintype "bidirectional"))
      (node (ref "B06") (pin "N1") (pinfunction "IN_N1") (pintype "input"))
    )
    (net (code "66") (name "I_IOP1") (class "Default")
      (node (ref "A01") (pin "K2") (pinfunction "P$2_K2") (pintype "bidirectional"))
      (node (ref "B01") (pin "K2") (pinfunction "P$2_K2") (pintype "bidirectional"))
      (node (ref "B06") (pin "A1") (pinfunction "IN1_A1") (pintype "input"))
    )
    (net (code "67") (name "I_IOP2") (class "Default")
      (node (ref "A01") (pin "M2") (pinfunction "P$2_M2") (pintype "bidirectional"))
      (node (ref "B01") (pin "M2") (pinfunction "P$2_M2") (pintype "bidirectional"))
      (node (ref "B06") (pin "D1") (pinfunction "IN_D1") (pintype "input"))
    )
    (net (code "68") (name "I_IOP4") (class "Default")
      (node (ref "A01") (pin "P2") (pinfunction "P$2_P2") (pintype "bidirectional"))
      (node (ref "B01") (pin "P2") (pinfunction "P$2_P2") (pintype "bidirectional"))
      (node (ref "B06") (pin "F1") (pinfunction "IN_F1") (pintype "input"))
    )
    (net (code "69") (name "I_IRQ") (class "Default")
      (node (ref "A03") (pin "M2") (pinfunction "P$2_M2") (pintype "bidirectional"))
      (node (ref "B03") (pin "M2") (pinfunction "P$2_M2") (pintype "bidirectional"))
      (node (ref "B18") (pin "F2") (pinfunction "OUT_F2") (pintype "output"))
    )
    (net (code "70") (name "I_LINE") (class "Default")
      (node (ref "A03") (pin "V2") (pinfunction "P$2_V2") (pintype "bidirectional"))
      (node (ref "B03") (pin "V2") (pinfunction "P$2_V2") (pintype "bidirectional"))
      (node (ref "B18") (pin "L2") (pinfunction "OUT_L2") (pintype "output"))
    )
    (net (code "71") (name "I_MB00") (class "Default")
      (node (ref "A02") (pin "B1") (pinfunction "P$2_B1") (pintype "bidirectional"))
      (node (ref "A06") (pin "B1") (pinfunction "CATHODE_B1") (pintype "passive"))
      (node (ref "A07") (pin "H2") (pinfunction "IN2_H2") (pintype "input"))
      (node (ref "B02") (pin "B1") (pinfunction "P$2_B1") (pintype "bidirectional"))
    )
    (net (code "72") (name "I_MB01") (class "Default")
      (node (ref "A02") (pin "D1") (pinfunction "P$2_D1") (pintype "bidirectional"))
      (node (ref "A06") (pin "D1") (pinfunction "CATHODE_D1") (pintype "passive"))
      (node (ref "A07") (pin "N2") (pinfunction "IN2_N2") (pintype "input"))
      (node (ref "B02") (pin "D1") (pinfunction "P$2_D1") (pintype "bidirectional"))
    )
    (net (code "73") (name "I_MB02") (class "Default")
      (node (ref "A02") (pin "E1") (pinfunction "P$2_E1") (pintype "bidirectional"))
      (node (ref "A06") (pin "E1") (pinfunction "CATHODE_E1") (pintype "passive"))
      (node (ref "A07") (pin "U2") (pinfunction "IN2_U2") (pintype "input"))
      (node (ref "B02") (pin "E1") (pinfunction "P$2_E1") (pintype "bidirectional"))
    )
    (net (code "74") (name "I_MB03") (class "Default")
      (node (ref "A02") (pin "J1") (pinfunction "P$2_J1") (pintype "bidirectional"))
      (node (ref "A06") (pin "J1") (pinfunction "CATHODE_J1") (pintype "passive"))
      (node (ref "A08") (pin "N2") (pinfunction "IN2_N2") (pintype "input"))
      (node (ref "B02") (pin "J1") (pinfunction "P$2_J1") (pintype "bidirectional"))
    )
    (net (code "75") (name "I_MB04") (class "Default")
      (node (ref "A02") (pin "M1") (pinfunction "P$2_M1") (pintype "bidirectional"))
      (node (ref "A06") (pin "M1") (pinfunction "CATHODE_M1") (pintype "passive"))
      (node (ref "A09") (pin "H2") (pinfunction "IN2_H2") (pintype "input"))
      (node (ref "B02") (pin "M1") (pinfunction "P$2_M1") (pintype "bidirectional"))
    )
    (net (code "76") (name "I_MB05") (class "Default")
      (node (ref "A02") (pin "S1") (pinfunction "P$2_S1") (pintype "bidirectional"))
      (node (ref "A06") (pin "S1") (pinfunction "CATHODE_S1") (pintype "passive"))
      (node (ref "A09") (pin "U2") (pinfunction "IN2_U2") (pintype "input"))
      (node (ref "B02") (pin "S1") (pinfunction "P$2_S1") (pintype "bidirectional"))
    )
    (net (code "77") (name "I_MB06") (class "Default")
      (node (ref "A02") (pin "E2") (pinfunction "P$2_E2") (pintype "bidirectional"))
      (node (ref "A06") (pin "E2") (pinfunction "CATHODE_E2") (pintype "passive"))
      (node (ref "A10") (pin "N2") (pinfunction "IN2_N2") (pintype "input"))
      (node (ref "B02") (pin "E2") (pinfunction "P$2_E2") (pintype "bidirectional"))
    )
    (net (code "78") (name "I_MB07") (class "Default")
      (node (ref "A02") (pin "K2") (pinfunction "P$2_K2") (pintype "bidirectional"))
      (node (ref "A06") (pin "K2") (pinfunction "CATHODE_K2") (pintype "passive"))
      (node (ref "A11") (pin "H2") (pinfunction "IN2_H2") (pintype "input"))
      (node (ref "B02") (pin "K2") (pinfunction "P$2_K2") (pintype "bidirectional"))
    )
    (net (code "79") (name "I_MB08") (class "Default")
      (node (ref "A02") (pin "P2") (pinfunction "P$2_P2") (pintype "bidirectional"))
      (node (ref "A06") (pin "P2") (pinfunction "CATHODE_P2") (pintype "passive"))
      (node (ref "A11") (pin "U2") (pinfunction "IN2_U2") (pintype "input"))
      (node (ref "B02") (pin "P2") (pinfunction "P$2_P2") (pintype "bidirectional"))
    )
    (net (code "80") (name "I_MB09") (class "Default")
      (node (ref "A02") (pin "S2") (pinfunction "P$2_S2") (pintype "bidirectional"))
      (node (ref "A06") (pin "S2") (pinfunction "CATHODE_S2") (pintype "passive"))
      (node (ref "A12") (pin "H2") (pinfunction "IN2_H2") (pintype "input"))
      (node (ref "B02") (pin "S2") (pinfunction "P$2_S2") (pintype "bidirectional"))
    )
    (net (code "81") (name "I_MB10") (class "Default")
      (node (ref "A02") (pin "T2") (pinfunction "P$2_T2") (pintype "bidirectional"))
      (node (ref "A06") (pin "T2") (pinfunction "CATHODE_T2") (pintype "passive"))
      (node (ref "A12") (pin "N2") (pinfunction "IN2_N2") (pintype "input"))
      (node (ref "B02") (pin "T2") (pinfunction "P$2_T2") (pintype "bidirectional"))
    )
    (net (code "82") (name "I_MB11") (class "Default")
      (node (ref "A02") (pin "V2") (pinfunction "P$2_V2") (pintype "bidirectional"))
      (node (ref "A06") (pin "V2") (pinfunction "CATHODE_V2") (pintype "passive"))
      (node (ref "A12") (pin "U2") (pinfunction "IN2_U2") (pintype "input"))
      (node (ref "B02") (pin "V2") (pinfunction "P$2_V2") (pintype "bidirectional"))
    )
    (net (code "83") (name "I_MBINCR") (class "Default")
      (node (ref "A04") (pin "T2") (pinfunction "P$2_T2") (pintype "bidirectional"))
      (node (ref "B04") (pin "T2") (pinfunction "P$2_T2") (pintype "bidirectional"))
      (node (ref "B19") (pin "D2") (pinfunction "OUT_D2") (pintype "output"))
    )
    (net (code "84") (name "I_RUN") (class "Default")
      (node (ref "A03") (pin "S2") (pinfunction "P$2_S2") (pintype "bidirectional"))
      (node (ref "B03") (pin "S2") (pinfunction "P$2_S2") (pintype "bidirectional"))
      (node (ref "B07") (pin "K2") (pinfunction "CATHODE_K2") (pintype "passive"))
      (node (ref "B14") (pin "H2") (pinfunction "IN2_H2") (pintype "input"))
    )
    (net (code "85") (name "I_SKIP") (class "Default")
      (node (ref "A03") (pin "K2") (pinfunction "P$2_K2") (pintype "bidirectional"))
      (node (ref "B03") (pin "K2") (pinfunction "P$2_K2") (pintype "bidirectional"))
      (node (ref "B18") (pin "D2") (pinfunction "OUT_D2") (pintype "output"))
    )
    (net (code "86") (name "I_TS1") (class "Default")
      (node (ref "A01") (pin "T2") (pinfunction "P$2_T2") (pintype "bidirectional"))
      (node (ref "B01") (pin "T2") (pinfunction "P$2_T2") (pintype "bidirectional"))
      (node (ref "B06") (pin "L1") (pinfunction "IN_L1") (pintype "input"))
    )
    (net (code "87") (name "I_TS3") (class "Default")
      (node (ref "A01") (pin "S2") (pinfunction "P$2_S2") (pintype "bidirectional"))
      (node (ref "B01") (pin "S2") (pinfunction "P$2_S2") (pintype "bidirectional"))
      (node (ref "B06") (pin "J1") (pinfunction "IN_J1") (pintype "input"))
    )
    (net (code "88") (name "I_TT_INST") (class "Default")
      (node (ref "A03") (pin "T2") (pinfunction "P$2_T2") (pintype "bidirectional"))
      (node (ref "B03") (pin "T2") (pinfunction "P$2_T2") (pintype "bidirectional"))
      (node (ref "B07") (pin "M2") (pinfunction "CATHODE_M2") (pintype "passive"))
      (node (ref "B14") (pin "N2") (pinfunction "IN2_N2") (pintype "input"))
    )
    (net (code "89") (name "I_WCOV") (class "Default")
      (node (ref "A05") (pin "P2") (pinfunction "P$2_P2") (pintype "bidirectional"))
      (node (ref "B05") (pin "P2") (pinfunction "P$2_P2") (pintype "bidirectional"))
      (node (ref "B07") (pin "T2") (pinfunction "CATHODE_T2") (pintype "passive"))
      (node (ref "B15") (pin "N2") (pinfunction "IN2_N2") (pintype "input"))
    )
    (net (code "90") (name "Net-(B06A-OUT)") (class "Default")
      (node (ref "B06") (pin "B1") (pinfunction "OUT_B1") (pintype "output"))
      (node (ref "B08") (pin "H2") (pinfunction "IN2_H2") (pintype "input"))
    )
    (net (code "91") (name "Net-(B06B-OUT)") (class "Default")
      (node (ref "B06") (pin "E1") (pinfunction "OUT_E1") (pintype "output"))
      (node (ref "B08") (pin "N2") (pinfunction "IN2_N2") (pintype "input"))
    )
    (net (code "92") (name "Net-(B06F-OUT)") (class "Default")
      (node (ref "B06") (pin "H1") (pinfunction "OUT_H1") (pintype "output"))
      (node (ref "B08") (pin "U2") (pinfunction "IN2_U2") (pintype "input"))
    )
    (net (code "93") (name "Net-(B06H-OUT)") (class "Default")
      (node (ref "B06") (pin "K1") (pinfunction "OUT_K1") (pintype "output"))
      (node (ref "B09") (pin "H2") (pinfunction "IN2_H2") (pintype "input"))
    )
    (net (code "94") (name "Net-(B06J-OUT)") (class "Default")
      (node (ref "B06") (pin "M1") (pinfunction "OUT_M1") (pintype "output"))
      (node (ref "B09") (pin "N2") (pinfunction "IN2_N2") (pintype "input"))
    )
    (net (code "95") (name "Net-(B06L-OUT)") (class "Default")
      (node (ref "B06") (pin "P1") (pinfunction "OUT_P1") (pintype "output"))
      (node (ref "B09") (pin "U2") (pinfunction "IN2_U2") (pintype "input"))
    )
    (net (code "96") (name "O_3CYCLE") (class "Default")
      (node (ref "A22") (pin "K2") (pinfunction "P$2_K2") (pintype "bidirectional"))
      (node (ref "B19") (pin "H2") (pinfunction "IN_H2") (pintype "input"))
    )
    (net (code "97") (name "O_AC00") (class "Default")
      (node (ref "A17") (pin "D2") (pinfunction "P$2_D2") (pintype "bidirectional"))
      (node (ref "B16") (pin "E2") (pinfunction "IN_E2") (pintype "input"))
    )
    (net (code "98") (name "O_AC01") (class "Default")
      (node (ref "A17") (pin "E2") (pinfunction "P$2_E2") (pintype "bidirectional"))
      (node (ref "B16") (pin "H2") (pinfunction "IN_H2") (pintype "input"))
    )
    (net (code "99") (name "O_AC02") (class "Default")
      (node (ref "A17") (pin "H2") (pinfunction "P$2_H2") (pintype "bidirectional"))
      (node (ref "B16") (pin "K2") (pinfunction "IN_K2") (pintype "input"))
    )
    (net (code "100") (name "O_AC03") (class "Default")
      (node (ref "A17") (pin "K2") (pinfunction "P$2_K2") (pintype "bidirectional"))
      (node (ref "B16") (pin "M2") (pinfunction "IN_M2") (pintype "input"))
    )
    (net (code "101") (name "O_AC04") (class "Default")
      (node (ref "A17") (pin "M2") (pinfunction "P$2_M2") (pintype "bidirectional"))
      (node (ref "B16") (pin "P2") (pinfunction "IN_P2") (pintype "input"))
    )
    (net (code "102") (name "O_AC05") (class "Default")
      (node (ref "A17") (pin "P2") (pinfunction "P$2_P2") (pintype "bidirectional"))
      (node (ref "B16") (pin "S2") (pinfunction "IN_S2") (pintype "input"))
    )
    (net (code "103") (name "O_AC06") (class "Default")
      (node (ref "A17") (pin "S2") (pinfunction "P$2_S2") (pintype "bidirectional"))
      (node (ref "B17") (pin "E2") (pinfunction "IN_E2") (pintype "input"))
    )
    (net (code "104") (name "O_AC07") (class "Default")
      (node (ref "A17") (pin "T2") (pinfunction "P$2_T2") (pintype "bidirectional"))
      (node (ref "B17") (pin "H2") (pinfunction "IN_H2") (pintype "input"))
    )
    (net (code "105") (name "O_AC08") (class "Default")
      (node (ref "A17") (pin "V2") (pinfunction "P$2_V2") (pintype "bidirectional"))
      (node (ref "B17") (pin "K2") (pinfunction "IN_K2") (pintype "input"))
    )
    (net (code "106") (name "O_AC09") (class "Default")
      (node (ref "A18") (pin "D2") (pinfunction "P$2_D2") (pintype "bidirectional"))
      (node (ref "B17") (pin "M2") (pinfunction "IN_M2") (pintype "input"))
    )
    (net (code "107") (name "O_AC10") (class "Default")
      (node (ref "A18") (pin "E2") (pinfunction "P$2_E2") (pintype "bidirectional"))
      (node (ref "B17") (pin "P2") (pinfunction "IN_P2") (pintype "input"))
    )
    (net (code "108") (name "O_AC11") (class "Default")
      (node (ref "A18") (pin "H2") (pinfunction "P$2_H2") (pintype "bidirectional"))
      (node (ref "B17") (pin "S2") (pinfunction "IN_S2") (pintype "input"))
    )
    (net (code "109") (name "O_ACCEPT") (class "Default")
      (node (ref "A20") (pin "S2") (pinfunction "P$2_S2") (pintype "bidirectional"))
      (node (ref "B15") (pin "D2") (pinfunction "OUT_D2") (pintype "output"))
    )
    (net (code "110") (name "O_ACCLR") (class "Default")
      (node (ref "A18") (pin "P2") (pinfunction "P$2_P2") (pintype "bidirectional"))
      (node (ref "B18") (pin "K2") (pinfunction "IN_K2") (pintype "input"))
    )
    (net (code "111") (name "O_ADD00") (class "Default")
      (node (ref "A19") (pin "D2") (pinfunction "P$2_D2") (pintype "bidirectional"))
      (node (ref "B20") (pin "E2") (pinfunction "IN_E2") (pintype "input"))
    )
    (net (code "112") (name "O_ADD01") (class "Default")
      (node (ref "A19") (pin "E2") (pinfunction "P$2_E2") (pintype "bidirectional"))
      (node (ref "B20") (pin "H2") (pinfunction "IN_H2") (pintype "input"))
    )
    (net (code "113") (name "O_ADD02") (class "Default")
      (node (ref "A19") (pin "H2") (pinfunction "P$2_H2") (pintype "bidirectional"))
      (node (ref "B20") (pin "K2") (pinfunction "IN_K2") (pintype "input"))
    )
    (net (code "114") (name "O_ADD03") (class "Default")
      (node (ref "A19") (pin "K2") (pinfunction "P$2_K2") (pintype "bidirectional"))
      (node (ref "B20") (pin "M2") (pinfunction "IN_M2") (pintype "input"))
    )
    (net (code "115") (name "O_ADD04") (class "Default")
      (node (ref "A19") (pin "M2") (pinfunction "P$2_M2") (pintype "bidirectional"))
      (node (ref "B20") (pin "P2") (pinfunction "IN_P2") (pintype "input"))
    )
    (net (code "116") (name "O_ADD05") (class "Default")
      (node (ref "A19") (pin "P2") (pinfunction "P$2_P2") (pintype "bidirectional"))
      (node (ref "B20") (pin "S2") (pinfunction "IN_S2") (pintype "input"))
    )
    (net (code "117") (name "O_ADD06") (class "Default")
      (node (ref "A19") (pin "S2") (pinfunction "P$2_S2") (pintype "bidirectional"))
      (node (ref "B21") (pin "E2") (pinfunction "IN_E2") (pintype "input"))
    )
    (net (code "118") (name "O_ADD07") (class "Default")
      (node (ref "A19") (pin "T2") (pinfunction "P$2_T2") (pintype "bidirectional"))
      (node (ref "B21") (pin "H2") (pinfunction "IN_H2") (pintype "input"))
    )
    (net (code "119") (name "O_ADD08") (class "Default")
      (node (ref "A19") (pin "V2") (pinfunction "P$2_V2") (pintype "bidirectional"))
      (node (ref "B21") (pin "K2") (pinfunction "IN_K2") (pintype "input"))
    )
    (net (code "120") (name "O_ADD09") (class "Default")
      (node (ref "A20") (pin "D2") (pinfunction "P$2_D2") (pintype "bidirectional"))
      (node (ref "B21") (pin "M2") (pinfunction "IN_M2") (pintype "input"))
    )
    (net (code "121") (name "O_ADD10") (class "Default")
      (node (ref "A20") (pin "E2") (pinfunction "P$2_E2") (pintype "bidirectional"))
      (node (ref "B21") (pin "P2") (pinfunction "IN_P2") (pintype "input"))
    )
    (net (code "122") (name "O_ADD11") (class "Default")
      (node (ref "A20") (pin "H2") (pinfunction "P$2_H2") (pintype "bidirectional"))
      (node (ref "B21") (pin "S2") (pinfunction "IN_S2") (pintype "input"))
    )
    (net (code "123") (name "O_BAC00") (class "Default")
      (node (ref "A13") (pin "D2") (pinfunction "P$2_D2") (pintype "bidirectional"))
      (node (ref "B10") (pin "D2") (pinfunction "OUT_D2") (pintype "output"))
    )
    (net (code "124") (name "O_BAC01") (class "Default")
      (node (ref "A13") (pin "E2") (pinfunction "P$2_E2") (pintype "bidirectional"))
      (node (ref "B10") (pin "K2") (pinfunction "OUT_K2") (pintype "output"))
    )
    (net (code "125") (name "O_BAC02") (class "Default")
      (node (ref "A13") (pin "H2") (pinfunction "P$2_H2") (pintype "bidirectional"))
      (node (ref "B10") (pin "S2") (pinfunction "OUT_S2") (pintype "output"))
    )
    (net (code "126") (name "O_BAC03") (class "Default")
      (node (ref "A13") (pin "K2") (pinfunction "P$2_K2") (pintype "bidirectional"))
      (node (ref "B11") (pin "D2") (pinfunction "OUT_D2") (pintype "output"))
    )
    (net (code "127") (name "O_BAC04") (class "Default")
      (node (ref "A13") (pin "M2") (pinfunction "P$2_M2") (pintype "bidirectional"))
      (node (ref "B11") (pin "K2") (pinfunction "OUT_K2") (pintype "output"))
    )
    (net (code "128") (name "O_BAC05") (class "Default")
      (node (ref "A13") (pin "P2") (pinfunction "P$2_P2") (pintype "bidirectional"))
      (node (ref "B11") (pin "S2") (pinfunction "OUT_S2") (pintype "output"))
    )
    (net (code "129") (name "O_BAC06") (class "Default")
      (node (ref "A13") (pin "S2") (pinfunction "P$2_S2") (pintype "bidirectional"))
      (node (ref "B12") (pin "D2") (pinfunction "OUT_D2") (pintype "output"))
    )
    (net (code "130") (name "O_BAC07") (class "Default")
      (node (ref "A13") (pin "T2") (pinfunction "P$2_T2") (pintype "bidirectional"))
      (node (ref "B12") (pin "K2") (pinfunction "OUT_K2") (pintype "output"))
    )
    (net (code "131") (name "O_BAC08") (class "Default")
      (node (ref "A13") (pin "V2") (pinfunction "P$2_V2") (pintype "bidirectional"))
      (node (ref "B12") (pin "S2") (pinfunction "OUT_S2") (pintype "output"))
    )
    (net (code "132") (name "O_BAC09") (class "Default")
      (node (ref "A14") (pin "D2") (pinfunction "P$2_D2") (pintype "bidirectional"))
      (node (ref "B13") (pin "D2") (pinfunction "OUT_D2") (pintype "output"))
    )
    (net (code "133") (name "O_BAC10") (class "Default")
      (node (ref "A14") (pin "E2") (pinfunction "P$2_E2") (pintype "bidirectional"))
      (node (ref "B13") (pin "K2") (pinfunction "OUT_K2") (pintype "output"))
    )
    (net (code "134") (name "O_BAC11") (class "Default")
      (node (ref "A14") (pin "H2") (pinfunction "P$2_H2") (pintype "bidirectional"))
      (node (ref "B13") (pin "S2") (pinfunction "OUT_S2") (pintype "output"))
    )
    (net (code "135") (name "O_BREAK") (class "Default")
      (node (ref "A20") (pin "P2") (pinfunction "P$2_P2") (pintype "bidirectional"))
      (node (ref "B14") (pin "S2") (pinfunction "OUT_S2") (pintype "output"))
    )
    (net (code "136") (name "O_BRKRQ") (class "Default")
      (node (ref "A20") (pin "K2") (pinfunction "P$2_K2") (pintype "bidirectional"))
      (node (ref "B18") (pin "P2") (pinfunction "IN_P2") (pintype "input"))
    )
    (net (code "137") (name "O_CAINCR") (class "Default")
      (node (ref "A22") (pin "M2") (pinfunction "P$2_M2") (pintype "bidirectional"))
      (node (ref "B19") (pin "K2") (pinfunction "IN_K2") (pintype "input"))
    )
    (net (code "138") (name "O_DATA00") (class "Default")
      (node (ref "A21") (pin "D2") (pinfunction "P$2_D2") (pintype "bidirectional"))
      (node (ref "B22") (pin "E2") (pinfunction "IN_E2") (pintype "input"))
    )
    (net (code "139") (name "O_DATA01") (class "Default")
      (node (ref "A21") (pin "E2") (pinfunction "P$2_E2") (pintype "bidirectional"))
      (node (ref "B22") (pin "H2") (pinfunction "IN_H2") (pintype "input"))
    )
    (net (code "140") (name "O_DATA02") (class "Default")
      (node (ref "A21") (pin "H2") (pinfunction "P$2_H2") (pintype "bidirectional"))
      (node (ref "B22") (pin "K2") (pinfunction "IN_K2") (pintype "input"))
    )
    (net (code "141") (name "O_DATA03") (class "Default")
      (node (ref "A21") (pin "K2") (pinfunction "P$2_K2") (pintype "bidirectional"))
      (node (ref "B22") (pin "M2") (pinfunction "IN_M2") (pintype "input"))
    )
    (net (code "142") (name "O_DATA04") (class "Default")
      (node (ref "A21") (pin "M2") (pinfunction "P$2_M2") (pintype "bidirectional"))
      (node (ref "B22") (pin "P2") (pinfunction "IN_P2") (pintype "input"))
    )
    (net (code "143") (name "O_DATA05") (class "Default")
      (node (ref "A21") (pin "P2") (pinfunction "P$2_P2") (pintype "bidirectional"))
      (node (ref "B22") (pin "S2") (pinfunction "IN_S2") (pintype "input"))
    )
    (net (code "144") (name "O_DATA06") (class "Default")
      (node (ref "A21") (pin "S2") (pinfunction "P$2_S2") (pintype "bidirectional"))
      (node (ref "B23") (pin "E2") (pinfunction "IN_E2") (pintype "input"))
    )
    (net (code "145") (name "O_DATA07") (class "Default")
      (node (ref "A21") (pin "T2") (pinfunction "P$2_T2") (pintype "bidirectional"))
      (node (ref "B23") (pin "H2") (pinfunction "IN_H2") (pintype "input"))
    )
    (net (code "146") (name "O_DATA08") (class "Default")
      (node (ref "A21") (pin "V2") (pinfunction "P$2_V2") (pintype "bidirectional"))
      (node (ref "B23") (pin "K2") (pinfunction "IN_K2") (pintype "input"))
    )
    (net (code "147") (name "O_DATA09") (class "Default")
      (node (ref "A22") (pin "D2") (pinfunction "P$2_D2") (pintype "bidirectional"))
      (node (ref "B23") (pin "M2") (pinfunction "IN_M2") (pintype "input"))
    )
    (net (code "148") (name "O_DATA10") (class "Default")
      (node (ref "A22") (pin "E2") (pinfunction "P$2_E2") (pintype "bidirectional"))
      (node (ref "B23") (pin "P2") (pinfunction "IN_P2") (pintype "input"))
    )
    (net (code "149") (name "O_DATA11") (class "Default")
      (node (ref "A22") (pin "H2") (pinfunction "P$2_H2") (pintype "bidirectional"))
      (node (ref "B23") (pin "S2") (pinfunction "IN_S2") (pintype "input"))
    )
    (net (code "150") (name "O_DATAIN") (class "Default")
      (node (ref "A20") (pin "M2") (pinfunction "P$2_M2") (pintype "bidirectional"))
      (node (ref "B18") (pin "S2") (pinfunction "IN_S2") (pintype "input"))
    )
    (net (code "151") (name "O_EXTA0") (class "Default")
      (node (ref "A23") (pin "H2") (pinfunction "P$2_H2") (pintype "bidirectional"))
      (node (ref "B19") (pin "S2") (pinfunction "IN_S2") (pintype "input"))
    )
    (net (code "152") (name "O_EXTA1") (class "Default")
      (node (ref "A23") (pin "E2") (pinfunction "P$2_E2") (pintype "bidirectional"))
      (node (ref "B19") (pin "P2") (pinfunction "IN_P2") (pintype "input"))
    )
    (net (code "153") (name "O_EXTA2") (class "Default")
      (node (ref "A23") (pin "D2") (pinfunction "P$2_D2") (pintype "bidirectional"))
      (node (ref "B19") (pin "M2") (pinfunction "IN_M2") (pintype "input"))
    )
    (net (code "154") (name "O_INIT") (class "Default")
      (node (ref "A14") (pin "V2") (pinfunction "P$2_V2") (pintype "bidirectional"))
      (node (ref "B09") (pin "S2") (pinfunction "OUT_S2") (pintype "output"))
    )
    (net (code "155") (name "O_IOP1") (class "Default")
      (node (ref "A14") (pin "K2") (pinfunction "P$2_K2") (pintype "bidirectional"))
      (node (ref "B08") (pin "D2") (pinfunction "OUT_D2") (pintype "output"))
    )
    (net (code "156") (name "O_IOP2") (class "Default")
      (node (ref "A14") (pin "M2") (pinfunction "P$2_M2") (pintype "bidirectional"))
      (node (ref "B08") (pin "K2") (pinfunction "OUT_K2") (pintype "output"))
    )
    (net (code "157") (name "O_IOP4") (class "Default")
      (node (ref "A14") (pin "P2") (pinfunction "P$2_P2") (pintype "bidirectional"))
      (node (ref "B08") (pin "S2") (pinfunction "OUT_S2") (pintype "output"))
    )
    (net (code "158") (name "O_IRQ") (class "Default")
      (node (ref "A18") (pin "M2") (pinfunction "P$2_M2") (pintype "bidirectional"))
      (node (ref "B18") (pin "H2") (pinfunction "IN_H2") (pintype "input"))
    )
    (net (code "159") (name "O_LINE") (class "Default")
      (node (ref "A18") (pin "V2") (pinfunction "P$2_V2") (pintype "bidirectional"))
      (node (ref "B18") (pin "M2") (pinfunction "IN_M2") (pintype "input"))
    )
    (net (code "160") (name "O_MB00") (class "Default")
      (node (ref "A07") (pin "D2") (pinfunction "OUT_D2") (pintype "output"))
      (node (ref "A15") (pin "D2") (pinfunction "P$2_D2") (pintype "bidirectional"))
    )
    (net (code "161") (name "O_MB01") (class "Default")
      (node (ref "A07") (pin "K2") (pinfunction "OUT_K2") (pintype "output"))
      (node (ref "A15") (pin "E2") (pinfunction "P$2_E2") (pintype "bidirectional"))
    )
    (net (code "162") (name "O_MB02") (class "Default")
      (node (ref "A07") (pin "S2") (pinfunction "OUT_S2") (pintype "output"))
      (node (ref "A15") (pin "H2") (pinfunction "P$2_H2") (pintype "bidirectional"))
    )
    (net (code "163") (name "O_MB03") (class "Default")
      (node (ref "A08") (pin "K2") (pinfunction "OUT_K2") (pintype "output"))
      (node (ref "A15") (pin "M2") (pinfunction "P$2_M2") (pintype "bidirectional"))
    )
    (net (code "164") (name "O_MB04") (class "Default")
      (node (ref "A09") (pin "D2") (pinfunction "OUT_D2") (pintype "output"))
      (node (ref "A15") (pin "S2") (pinfunction "P$2_S2") (pintype "bidirectional"))
    )
    (net (code "165") (name "O_MB05") (class "Default")
      (node (ref "A09") (pin "S2") (pinfunction "OUT_S2") (pintype "output"))
      (node (ref "A15") (pin "V2") (pinfunction "P$2_V2") (pintype "bidirectional"))
    )
    (net (code "166") (name "O_MB06") (class "Default")
      (node (ref "A10") (pin "K2") (pinfunction "OUT_K2") (pintype "output"))
      (node (ref "A16") (pin "E2") (pinfunction "P$2_E2") (pintype "bidirectional"))
    )
    (net (code "167") (name "O_MB07") (class "Default")
      (node (ref "A11") (pin "D2") (pinfunction "OUT_D2") (pintype "output"))
      (node (ref "A16") (pin "K2") (pinfunction "P$2_K2") (pintype "bidirectional"))
    )
    (net (code "168") (name "O_MB08") (class "Default")
      (node (ref "A11") (pin "S2") (pinfunction "OUT_S2") (pintype "output"))
      (node (ref "A16") (pin "P2") (pinfunction "P$2_P2") (pintype "bidirectional"))
    )
    (net (code "169") (name "O_MB09") (class "Default")
      (node (ref "A12") (pin "D2") (pinfunction "OUT_D2") (pintype "output"))
      (node (ref "A16") (pin "S2") (pinfunction "P$2_S2") (pintype "bidirectional"))
    )
    (net (code "170") (name "O_MB10") (class "Default")
      (node (ref "A12") (pin "K2") (pinfunction "OUT_K2") (pintype "output"))
      (node (ref "A16") (pin "T2") (pinfunction "P$2_T2") (pintype "bidirectional"))
    )
    (net (code "171") (name "O_MB11") (class "Default")
      (node (ref "A12") (pin "S2") (pinfunction "OUT_S2") (pintype "output"))
      (node (ref "A16") (pin "V2") (pinfunction "P$2_V2") (pintype "bidirectional"))
    )
    (net (code "172") (name "O_MBINCR") (class "Default")
      (node (ref "A20") (pin "T2") (pinfunction "P$2_T2") (pintype "bidirectional"))
      (node (ref "B19") (pin "E2") (pinfunction "IN_E2") (pintype "input"))
    )
    (net (code "173") (name "O_RUN") (class "Default")
      (node (ref "A18") (pin "S2") (pinfunction "P$2_S2") (pintype "bidirectional"))
      (node (ref "B14") (pin "D2") (pinfunction "OUT_D2") (pintype "output"))
    )
    (net (code "174") (name "O_SKIP") (class "Default")
      (node (ref "A18") (pin "K2") (pinfunction "P$2_K2") (pintype "bidirectional"))
      (node (ref "B18") (pin "E2") (pinfunction "IN_E2") (pintype "input"))
    )
    (net (code "175") (name "O_TS1") (class "Default")
      (node (ref "A14") (pin "T2") (pinfunction "P$2_T2") (pintype "bidirectional"))
      (node (ref "B09") (pin "K2") (pinfunction "OUT_K2") (pintype "output"))
    )
    (net (code "176") (name "O_TS3") (class "Default")
      (node (ref "A14") (pin "S2") (pinfunction "P$2_S2") (pintype "bidirectional"))
      (node (ref "B09") (pin "D2") (pinfunction "OUT_D2") (pintype "output"))
    )
    (net (code "177") (name "O_TT_INST") (class "Default")
      (node (ref "A18") (pin "T2") (pinfunction "P$2_T2") (pintype "bidirectional"))
      (node (ref "B14") (pin "K2") (pinfunction "OUT_K2") (pintype "output"))
    )
    (net (code "178") (name "O_WCOV") (class "Default")
      (node (ref "A22") (pin "P2") (pinfunction "P$2_P2") (pintype "bidirectional"))
      (node (ref "B15") (pin "K2") (pinfunction "OUT_K2") (pintype "output"))
    )
    (net (code "180") (name "unconnected-(A07A-SLOW-PadE2)") (class "Default")
      (node (ref "A07") (pin "E2") (pinfunction "SLOW_E2") (pintype "passive"))
    )
    (net (code "181") (name "unconnected-(A07D-SLOW-PadL2)") (class "Default")
      (node (ref "A07") (pin "L2") (pinfunction "SLOW_L2") (pintype "passive"))
    )
    (net (code "182") (name "unconnected-(A07E-SLOW-PadR2)") (class "Default")
      (node (ref "A07") (pin "R2") (pinfunction "SLOW_R2") (pintype "passive"))
    )
    (net (code "183") (name "unconnected-(A08A-SLOW-PadE2)") (class "Default")
      (node (ref "A08") (pin "E2") (pinfunction "SLOW_E2") (pintype "passive"))
    )
    (net (code "184") (name "unconnected-(A08D-SLOW-PadL2)") (class "Default")
      (node (ref "A08") (pin "L2") (pinfunction "SLOW_L2") (pintype "passive"))
    )
    (net (code "185") (name "unconnected-(A08E-SLOW-PadR2)") (class "Default")
      (node (ref "A08") (pin "R2") (pinfunction "SLOW_R2") (pintype "passive"))
    )
    (net (code "186") (name "unconnected-(A09A-SLOW-PadE2)") (class "Default")
      (node (ref "A09") (pin "E2") (pinfunction "SLOW_E2") (pintype "passive"))
    )
    (net (code "187") (name "unconnected-(A09D-SLOW-PadL2)") (class "Default")
      (node (ref "A09") (pin "L2") (pinfunction "SLOW_L2") (pintype "passive"))
    )
    (net (code "188") (name "unconnected-(A09E-SLOW-PadR2)") (class "Default")
      (node (ref "A09") (pin "R2") (pinfunction "SLOW_R2") (pintype "passive"))
    )
    (net (code "189") (name "unconnected-(A10A-SLOW-PadE2)") (class "Default")
      (node (ref "A10") (pin "E2") (pinfunction "SLOW_E2") (pintype "passive"))
    )
    (net (code "190") (name "unconnected-(A10D-SLOW-PadL2)") (class "Default")
      (node (ref "A10") (pin "L2") (pinfunction "SLOW_L2") (pintype "passive"))
    )
    (net (code "191") (name "unconnected-(A10E-SLOW-PadR2)") (class "Default")
      (node (ref "A10") (pin "R2") (pinfunction "SLOW_R2") (pintype "passive"))
    )
    (net (code "192") (name "unconnected-(A11A-SLOW-PadE2)") (class "Default")
      (node (ref "A11") (pin "E2") (pinfunction "SLOW_E2") (pintype "passive"))
    )
    (net (code "193") (name "unconnected-(A11D-SLOW-PadL2)") (class "Default")
      (node (ref "A11") (pin "L2") (pinfunction "SLOW_L2") (pintype "passive"))
    )
    (net (code "194") (name "unconnected-(A11E-SLOW-PadR2)") (class "Default")
      (node (ref "A11") (pin "R2") (pinfunction "SLOW_R2") (pintype "passive"))
    )
    (net (code "195") (name "unconnected-(A12A-SLOW-PadE2)") (class "Default")
      (node (ref "A12") (pin "E2") (pinfunction "SLOW_E2") (pintype "passive"))
    )
    (net (code "196") (name "unconnected-(A12D-SLOW-PadL2)") (class "Default")
      (node (ref "A12") (pin "L2") (pinfunction "SLOW_L2") (pintype "passive"))
    )
    (net (code "197") (name "unconnected-(A12E-SLOW-PadR2)") (class "Default")
      (node (ref "A12") (pin "R2") (pinfunction "SLOW_R2") (pintype "passive"))
    )
    (net (code "198") (name "unconnected-(B08A-SLOW-PadE2)") (class "Default")
      (node (ref "B08") (pin "E2") (pinfunction "SLOW_E2") (pintype "passive"))
    )
    (net (code "199") (name "unconnected-(B08D-SLOW-PadL2)") (class "Default")
      (node (ref "B08") (pin "L2") (pinfunction "SLOW_L2") (pintype "passive"))
    )
    (net (code "200") (name "unconnected-(B08E-SLOW-PadR2)") (class "Default")
      (node (ref "B08") (pin "R2") (pinfunction "SLOW_R2") (pintype "passive"))
    )
    (net (code "201") (name "unconnected-(B09A-SLOW-PadE2)") (class "Default")
      (node (ref "B09") (pin "E2") (pinfunction "SLOW_E2") (pintype "passive"))
    )
    (net (code "202") (name "unconnected-(B09D-SLOW-PadL2)") (class "Default")
      (node (ref "B09") (pin "L2") (pinfunction "SLOW_L2") (pintype "passive"))
    )
    (net (code "203") (name "unconnected-(B09E-SLOW-PadR2)") (class "Default")
      (node (ref "B09") (pin "R2") (pinfunction "SLOW_R2") (pintype "passive"))
    )
    (net (code "204") (name "unconnected-(B10A-SLOW-PadE2)") (class "Default")
      (node (ref "B10") (pin "E2") (pinfunction "SLOW_E2") (pintype "passive"))
    )
    (net (code "205") (name "unconnected-(B10D-SLOW-PadL2)") (class "Default")
      (node (ref "B10") (pin "L2") (pinfunction "SLOW_L2") (pintype "passive"))
    )
    (net (code "206") (name "unconnected-(B10E-SLOW-PadR2)") (class "Default")
      (node (ref "B10") (pin "R2") (pinfunction "SLOW_R2") (pintype "passive"))
    )
    (net (code "207") (name "unconnected-(B11A-SLOW-PadE2)") (class "Default")
      (node (ref "B11") (pin "E2") (pinfunction "SLOW_E2") (pintype "passive"))
    )
    (net (code "208") (name "unconnected-(B11D-SLOW-PadL2)") (class "Default")
      (node (ref "B11") (pin "L2") (pinfunction "SLOW_L2") (pintype "passive"))
    )
    (net (code "209") (name "unconnected-(B11E-SLOW-PadR2)") (class "Default")
      (node (ref "B11") (pin "R2") (pinfunction "SLOW_R2") (pintype "passive"))
    )
    (net (code "210") (name "unconnected-(B12A-SLOW-PadE2)") (class "Default")
      (node (ref "B12") (pin "E2") (pinfunction "SLOW_E2") (pintype "passive"))
    )
    (net (code "211") (name "unconnected-(B12D-SLOW-PadL2)") (class "Default")
      (node (ref "B12") (pin "L2") (pinfunction "SLOW_L2") (pintype "passive"))
    )
    (net (code "212") (name "unconnected-(B12E-SLOW-PadR2)") (class "Default")
      (node (ref "B12") (pin "R2") (pinfunction "SLOW_R2") (pintype "passive"))
    )
    (net (code "213") (name "unconnected-(B13A-SLOW-PadE2)") (class "Default")
      (node (ref "B13") (pin "E2") (pinfunction "SLOW_E2") (pintype "passive"))
    )
    (net (code "214") (name "unconnected-(B13D-SLOW-PadL2)") (class "Default")
      (node (ref "B13") (pin "L2") (pinfunction "SLOW_L2") (pintype "passive"))
    )
    (net (code "215") (name "unconnected-(B13E-SLOW-PadR2)") (class "Default")
      (node (ref "B13") (pin "R2") (pinfunction "SLOW_R2") (pintype "passive"))
    )
    (net (code "216") (name "unconnected-(B14A-SLOW-PadE2)") (class "Default")
      (node (ref "B14") (pin "E2") (pinfunction "SLOW_E2") (pintype "passive"))
    )
    (net (code "217") (name "unconnected-(B14D-SLOW-PadL2)") (class "Default")
      (node (ref "B14") (pin "L2") (pinfunction "SLOW_L2") (pintype "passive"))
    )
    (net (code "218") (name "unconnected-(B14E-SLOW-PadR2)") (class "Default")
      (node (ref "B14") (pin "R2") (pinfunction "SLOW_R2") (pintype "passive"))
    )
    (net (code "219") (name "unconnected-(B15A-SLOW-PadE2)") (class "Default")
      (node (ref "B15") (pin "E2") (pinfunction "SLOW_E2") (pintype "passive"))
    )
    (net (code "220") (name "unconnected-(B15D-SLOW-PadL2)") (class "Default")
      (node (ref "B15") (pin "L2") (pinfunction "SLOW_L2") (pintype "passive"))
    )
    (net (code "221") (name "~{I_MB03}") (class "Default")
      (node (ref "A02") (pin "H1") (pinfunction "P$2_H1") (pintype "bidirectional"))
      (node (ref "A06") (pin "H1") (pinfunction "CATHODE_H1") (pintype "passive"))
      (node (ref "A08") (pin "H2") (pinfunction "IN2_H2") (pintype "input"))
      (node (ref "B02") (pin "H1") (pinfunction "P$2_H1") (pintype "bidirectional"))
    )
    (net (code "222") (name "~{I_MB04}") (class "Default")
      (node (ref "A02") (pin "L1") (pinfunction "P$2_L1") (pintype "bidirectional"))
      (node (ref "A06") (pin "L1") (pinfunction "CATHODE_L1") (pintype "passive"))
      (node (ref "A08") (pin "U2") (pinfunction "IN2_U2") (pintype "input"))
      (node (ref "B02") (pin "L1") (pinfunction "P$2_L1") (pintype "bidirectional"))
    )
    (net (code "223") (name "~{I_MB05}") (class "Default")
      (node (ref "A02") (pin "P1") (pinfunction "P$2_P1") (pintype "bidirectional"))
      (node (ref "A06") (pin "P1") (pinfunction "CATHODE_P1") (pintype "passive"))
      (node (ref "A09") (pin "N2") (pinfunction "IN2_N2") (pintype "input"))
      (node (ref "B02") (pin "P1") (pinfunction "P$2_P1") (pintype "bidirectional"))
    )
    (net (code "224") (name "~{I_MB06}") (class "Default")
      (node (ref "A02") (pin "D2") (pinfunction "P$2_D2") (pintype "bidirectional"))
      (node (ref "A06") (pin "D2") (pinfunction "CATHODE_D2") (pintype "passive"))
      (node (ref "A10") (pin "H2") (pinfunction "IN2_H2") (pintype "input"))
      (node (ref "B02") (pin "D2") (pinfunction "P$2_D2") (pintype "bidirectional"))
    )
    (net (code "225") (name "~{I_MB07}") (class "Default")
      (node (ref "A02") (pin "H2") (pinfunction "P$2_H2") (pintype "bidirectional"))
      (node (ref "A06") (pin "H2") (pinfunction "CATHODE_H2") (pintype "passive"))
      (node (ref "A10") (pin "U2") (pinfunction "IN2_U2") (pintype "input"))
      (node (ref "B02") (pin "H2") (pinfunction "P$2_H2") (pintype "bidirectional"))
    )
    (net (code "226") (name "~{I_MB08}") (class "Default")
      (node (ref "A02") (pin "M2") (pinfunction "P$2_M2") (pintype "bidirectional"))
      (node (ref "A06") (pin "M2") (pinfunction "CATHODE_M2") (pintype "passive"))
      (node (ref "A11") (pin "N2") (pinfunction "IN2_N2") (pintype "input"))
      (node (ref "B02") (pin "M2") (pinfunction "P$2_M2") (pintype "bidirectional"))
    )
    (net (code "227") (name "~{O_MB03}") (class "Default")
      (node (ref "A08") (pin "D2") (pinfunction "OUT_D2") (pintype "output"))
      (node (ref "A15") (pin "K2") (pinfunction "P$2_K2") (pintype "bidirectional"))
    )
    (net (code "228") (name "~{O_MB04}") (class "Default")
      (node (ref "A08") (pin "S2") (pinfunction "OUT_S2") (pintype "output"))
      (node (ref "A15") (pin "P2") (pinfunction "P$2_P2") (pintype "bidirectional"))
    )
    (net (code "229") (name "~{O_MB05}") (class "Default")
      (node (ref "A09") (pin "K2") (pinfunction "OUT_K2") (pintype "output"))
      (node (ref "A15") (pin "T2") (pinfunction "P$2_T2") (pintype "bidirectional"))
    )
    (net (code "230") (name "~{O_MB06}") (class "Default")
      (node (ref "A10") (pin "D2") (pinfunction "OUT_D2") (pintype "output"))
      (node (ref "A16") (pin "D2") (pinfunction "P$2_D2") (pintype "bidirectional"))
    )
    (net (code "231") (name "~{O_MB07}") (class "Default")
      (node (ref "A10") (pin "S2") (pinfunction "OUT_S2") (pintype "output"))
      (node (ref "A16") (pin "H2") (pinfunction "P$2_H2") (pintype "bidirectional"))
    )
    (net (code "232") (name "~{O_MB08}") (class "Default")
      (node (ref "A11") (pin "K2") (pinfunction "OUT_K2") (pintype "output"))
      (node (ref "A16") (pin "M2") (pinfunction "P$2_M2") (pintype "bidirectional"))
    )
  )
)
